# PCB_3U_VHDCI_Baseboard.net
KiCad netlist of a schematic drawn in Altium Designer
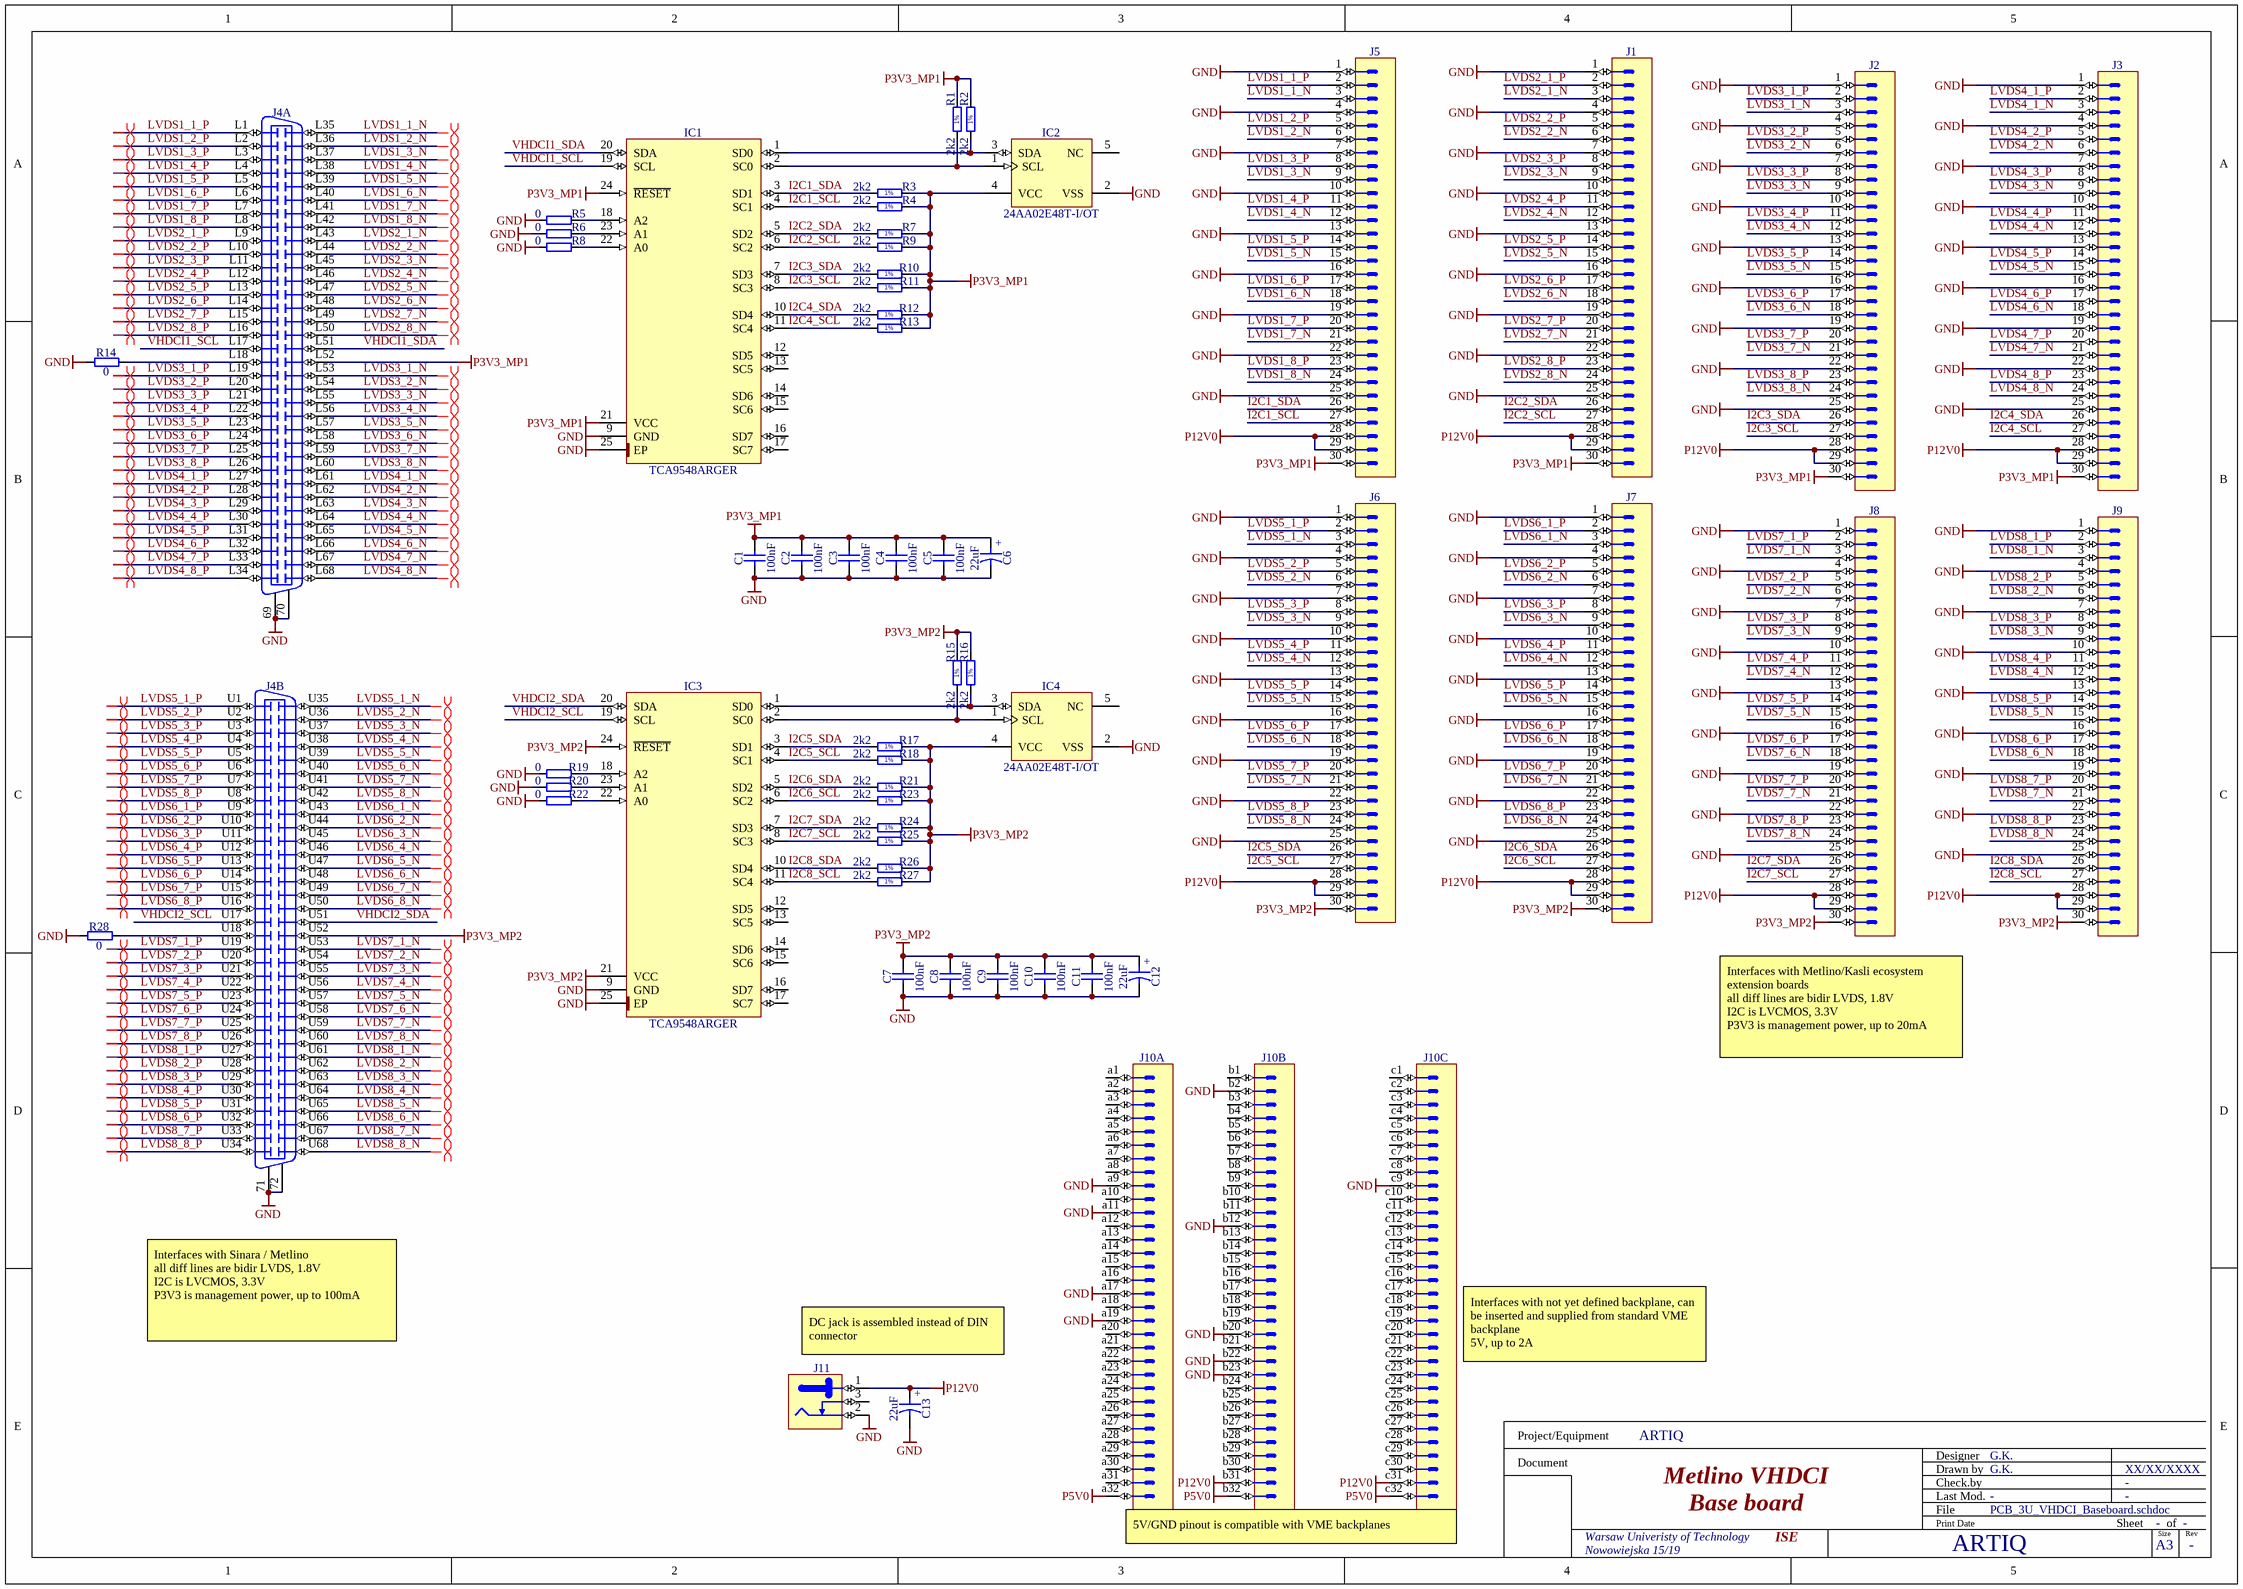
[diagram p0: PCB_3U_VHDCI_Baseboard.schdoc]

(export (version "E")
  (design (tool "Eeschema 10.0.6"))
  (components
    (comp (ref "C1")
      (value "100nF")
      (footprint "CAPC1005X55N")
      (description "Non-polarised capacitor")
      (fields
        (field (name "PART NUMBER") "CC0402_100NF_16V_10%_X5R")
        (field (name "VOLTAGE") "16V")
        (field (name "AUTHOR") "CERN DEM JLC")
      )
      (libsource (lib "Capacitors") (part "Capacitor - non polarized"))
    )
    (comp (ref "C2")
      (value "100nF")
      (footprint "CAPC1005X55N")
      (description "Non-polarised capacitor")
      (fields
        (field (name "PART NUMBER") "CC0402_100NF_16V_10%_X5R")
        (field (name "VOLTAGE") "16V")
        (field (name "AUTHOR") "CERN DEM JLC")
      )
      (libsource (lib "Capacitors") (part "Capacitor - non polarized"))
    )
    (comp (ref "C3")
      (value "100nF")
      (footprint "CAPC1005X55N")
      (description "Non-polarised capacitor")
      (fields
        (field (name "PART NUMBER") "CC0402_100NF_16V_10%_X5R")
        (field (name "VOLTAGE") "16V")
        (field (name "AUTHOR") "CERN DEM JLC")
      )
      (libsource (lib "Capacitors") (part "Capacitor - non polarized"))
    )
    (comp (ref "C4")
      (value "100nF")
      (footprint "CAPC1005X55N")
      (description "Non-polarised capacitor")
      (fields
        (field (name "PART NUMBER") "CC0402_100NF_16V_10%_X5R")
        (field (name "VOLTAGE") "16V")
        (field (name "AUTHOR") "CERN DEM JLC")
      )
      (libsource (lib "Capacitors") (part "Capacitor - non polarized"))
    )
    (comp (ref "C5")
      (value "100nF")
      (footprint "CAPC1005X55N")
      (description "Non-polarised capacitor")
      (fields
        (field (name "PART NUMBER") "CC0402_100NF_16V_10%_X5R")
        (field (name "VOLTAGE") "16V")
        (field (name "AUTHOR") "CERN DEM JLC")
      )
      (libsource (lib "Capacitors") (part "Capacitor - non polarized"))
    )
    (comp (ref "C6")
      (value "22uF")
      (footprint "CAPAE530X540N")
      (description "Polarised capacitor")
      (fields
        (field (name "PART NUMBER") "CAE530-540_22UF_16V_20%")
        (field (name "VOLTAGE") "16V")
        (field (name "AUTHOR") "CERN DEM JLC")
      )
      (libsource (lib "Capacitors") (part "Capacitor - polarized"))
    )
    (comp (ref "C7")
      (value "100nF")
      (footprint "CAPC1005X55N")
      (description "Non-polarised capacitor")
      (fields
        (field (name "PART NUMBER") "CC0402_100NF_16V_10%_X5R")
        (field (name "VOLTAGE") "16V")
        (field (name "AUTHOR") "CERN DEM JLC")
      )
      (libsource (lib "Capacitors") (part "Capacitor - non polarized"))
    )
    (comp (ref "C8")
      (value "100nF")
      (footprint "CAPC1005X55N")
      (description "Non-polarised capacitor")
      (fields
        (field (name "PART NUMBER") "CC0402_100NF_16V_10%_X5R")
        (field (name "VOLTAGE") "16V")
        (field (name "AUTHOR") "CERN DEM JLC")
      )
      (libsource (lib "Capacitors") (part "Capacitor - non polarized"))
    )
    (comp (ref "C9")
      (value "100nF")
      (footprint "CAPC1005X55N")
      (description "Non-polarised capacitor")
      (fields
        (field (name "PART NUMBER") "CC0402_100NF_16V_10%_X5R")
        (field (name "VOLTAGE") "16V")
        (field (name "AUTHOR") "CERN DEM JLC")
      )
      (libsource (lib "Capacitors") (part "Capacitor - non polarized"))
    )
    (comp (ref "C10")
      (value "100nF")
      (footprint "CAPC1005X55N")
      (description "Non-polarised capacitor")
      (fields
        (field (name "PART NUMBER") "CC0402_100NF_16V_10%_X5R")
        (field (name "VOLTAGE") "16V")
        (field (name "AUTHOR") "CERN DEM JLC")
      )
      (libsource (lib "Capacitors") (part "Capacitor - non polarized"))
    )
    (comp (ref "C11")
      (value "100nF")
      (footprint "CAPC1005X55N")
      (description "Non-polarised capacitor")
      (fields
        (field (name "PART NUMBER") "CC0402_100NF_16V_10%_X5R")
        (field (name "VOLTAGE") "16V")
        (field (name "AUTHOR") "CERN DEM JLC")
      )
      (libsource (lib "Capacitors") (part "Capacitor - non polarized"))
    )
    (comp (ref "C12")
      (value "22uF")
      (footprint "CAPAE530X540N")
      (description "Polarised capacitor")
      (fields
        (field (name "PART NUMBER") "CAE530-540_22UF_16V_20%")
        (field (name "VOLTAGE") "16V")
        (field (name "AUTHOR") "CERN DEM JLC")
      )
      (libsource (lib "Capacitors") (part "Capacitor - polarized"))
    )
    (comp (ref "C13")
      (value "22uF")
      (footprint "CAPAE530X540N")
      (description "Polarised capacitor")
      (fields
        (field (name "PART NUMBER") "CAE530-540_22UF_16V_20%")
        (field (name "VOLTAGE") "16V")
        (field (name "AUTHOR") "CERN DEM JLC")
      )
      (libsource (lib "Capacitors") (part "Capacitor - polarized"))
    )
    (comp (ref "IC1")
      (value "TCA9548ARGER")
      (footprint "QFN50P400X400X100-25N-S220")
      (description "Low Voltage 8-Channel I2C Switch With Reset")
      (fields (field (name "MANUFACTURER") "TEXAS INSTRUMENTS") (field (name "AUTHOR") "CERN DEM JLC"))
      (libsource (lib "ICs And Semiconductors") (part "TCA9548ARGER"))
    )
    (comp (ref "IC2")
      (value "24AA02E48T-I/OT")
      (footprint "SOT95P280X145-5N")
      (description "1.7V-5.5V, 2K I2C Serial EEPROM With EUI-48 Node Identity")
      (fields (field (name "MANUFACTURER") "MICROCHIP TECHNOLOGY") (field (name "AUTHOR") "CERN DEM MR"))
      (libsource (lib "ICs And Semiconductors") (part "24AA02E48T-I/OT"))
    )
    (comp (ref "IC3")
      (value "TCA9548ARGER")
      (footprint "QFN50P400X400X100-25N-S220")
      (description "Low Voltage 8-Channel I2C Switch With Reset")
      (fields (field (name "MANUFACTURER") "TEXAS INSTRUMENTS") (field (name "AUTHOR") "CERN DEM JLC"))
      (libsource (lib "ICs And Semiconductors") (part "TCA9548ARGER"))
    )
    (comp (ref "IC4")
      (value "24AA02E48T-I/OT")
      (footprint "SOT95P280X145-5N")
      (description "1.7V-5.5V, 2K I2C Serial EEPROM With EUI-48 Node Identity")
      (fields (field (name "MANUFACTURER") "MICROCHIP TECHNOLOGY") (field (name "AUTHOR") "CERN DEM MR"))
      (libsource (lib "ICs And Semiconductors") (part "24AA02E48T-I/OT"))
    )
    (comp (ref "J1")
      (value "~")
      (footprint "3M_N2530-6002RB")
      (description "Connector 30 Male")
      (fields
        (field (name "PART NUMBER") "3M_N2530-6002RB")
        (field (name "MANUFACTURER") "3M")
        (field (name "AUTHOR") "CERN DEM JLC")
      )
      (libsource (lib "Connectors") (part "Connector 30 Male"))
    )
    (comp (ref "J2")
      (value "~")
      (footprint "3M_N2530-6002RB")
      (description "Connector 30 Male")
      (fields
        (field (name "PART NUMBER") "3M_N2530-6002RB")
        (field (name "MANUFACTURER") "3M")
        (field (name "AUTHOR") "CERN DEM JLC")
      )
      (libsource (lib "Connectors") (part "Connector 30 Male"))
    )
    (comp (ref "J3")
      (value "~")
      (footprint "3M_N2530-6002RB")
      (description "Connector 30 Male")
      (fields
        (field (name "PART NUMBER") "3M_N2530-6002RB")
        (field (name "MANUFACTURER") "3M")
        (field (name "AUTHOR") "CERN DEM JLC")
      )
      (libsource (lib "Connectors") (part "Connector 30 Male"))
    )
    (comp (ref "J4")
      (value "VHDCI")
      (footprint "MOLEX_74337-0015")
      (description "Very High Density Cable Interconnect (VHDCI ) 2x68 Female")
      (fields
        (field (name "PART NUMBER") "MOLEX_74337-0015")
        (field (name "MANUFACTURER") "MOLEX")
        (field (name "AUTHOR") "CERN DEM JLC")
      )
      (libsource (lib "Connectors") (part "Connector VHDCI 2x68 Female"))
    )
    (comp (ref "J5")
      (value "~")
      (footprint "3M_N2530-6002RB")
      (description "Connector 30 Male")
      (fields
        (field (name "PART NUMBER") "3M_N2530-6002RB")
        (field (name "MANUFACTURER") "3M")
        (field (name "AUTHOR") "CERN DEM JLC")
      )
      (libsource (lib "Connectors") (part "Connector 30 Male"))
    )
    (comp (ref "J6")
      (value "~")
      (footprint "3M_N2530-6002RB")
      (description "Connector 30 Male")
      (fields
        (field (name "PART NUMBER") "3M_N2530-6002RB")
        (field (name "MANUFACTURER") "3M")
        (field (name "AUTHOR") "CERN DEM JLC")
      )
      (libsource (lib "Connectors") (part "Connector 30 Male"))
    )
    (comp (ref "J7")
      (value "~")
      (footprint "3M_N2530-6002RB")
      (description "Connector 30 Male")
      (fields
        (field (name "PART NUMBER") "3M_N2530-6002RB")
        (field (name "MANUFACTURER") "3M")
        (field (name "AUTHOR") "CERN DEM JLC")
      )
      (libsource (lib "Connectors") (part "Connector 30 Male"))
    )
    (comp (ref "J8")
      (value "~")
      (footprint "3M_N2530-6002RB")
      (description "Connector 30 Male")
      (fields
        (field (name "PART NUMBER") "3M_N2530-6002RB")
        (field (name "MANUFACTURER") "3M")
        (field (name "AUTHOR") "CERN DEM JLC")
      )
      (libsource (lib "Connectors") (part "Connector 30 Male"))
    )
    (comp (ref "J9")
      (value "~")
      (footprint "3M_N2530-6002RB")
      (description "Connector 30 Male")
      (fields
        (field (name "PART NUMBER") "3M_N2530-6002RB")
        (field (name "MANUFACTURER") "3M")
        (field (name "AUTHOR") "CERN DEM JLC")
      )
      (libsource (lib "Connectors") (part "Connector 30 Male"))
    )
    (comp (ref "J10")
      (value "DIN 41612 Type C")
      (footprint "HARTING_09 03 196 2921")
      (description "Connector 96abc male (3x32)")
      (fields
        (field (name "PART NUMBER") "HARTING_09 03 196 2921")
        (field (name "MANUFACTURER") "HARTING")
        (field (name "AUTHOR") "CERN DEM JLC")
      )
      (libsource (lib "Connectors") (part "Connector 96abc male (3x32)"))
    )
    (comp (ref "J11")
      (value "Jack")
      (footprint "CUI_PJ-102BH")
      (description "2.5 mm Center Pin, 5A, 24V Right Angle, Through Hole, Tapered Pins, DC Power Jack Connector")
      (fields
        (field (name "PART NUMBER") "CUI_PJ-102BH")
        (field (name "MANUFACTURER") "CUI INC.")
        (field (name "AUTHOR") "CERN DEM JLC")
      )
      (libsource (lib "Connectors") (part "CUI_PJ-102BH"))
    )
    (comp (ref "R1")
      (value "2k2")
      (footprint "RESC1005X40N")
      (description "Resistor - 1%")
      (fields
        (field (name "PART NUMBER") "R0402_2K2_1%_0.0625W_100PPM")
        (field (name "POWER") "0.0625W")
        (field (name "AUTHOR") "CERN DEM JLC")
      )
      (libsource (lib "Resistors") (part "Resistor - 1%"))
    )
    (comp (ref "R2")
      (value "2k2")
      (footprint "RESC1005X40N")
      (description "Resistor - 1%")
      (fields
        (field (name "PART NUMBER") "R0402_2K2_1%_0.0625W_100PPM")
        (field (name "POWER") "0.0625W")
        (field (name "AUTHOR") "CERN DEM JLC")
      )
      (libsource (lib "Resistors") (part "Resistor - 1%"))
    )
    (comp (ref "R3")
      (value "2k2")
      (footprint "RESC1005X40N")
      (description "Resistor - 1%")
      (fields
        (field (name "PART NUMBER") "R0402_2K2_1%_0.0625W_100PPM")
        (field (name "POWER") "0.0625W")
        (field (name "AUTHOR") "CERN DEM JLC")
      )
      (libsource (lib "Resistors") (part "Resistor - 1%"))
    )
    (comp (ref "R4")
      (value "2k2")
      (footprint "RESC1005X40N")
      (description "Resistor - 1%")
      (fields
        (field (name "PART NUMBER") "R0402_2K2_1%_0.0625W_100PPM")
        (field (name "POWER") "0.0625W")
        (field (name "AUTHOR") "CERN DEM JLC")
      )
      (libsource (lib "Resistors") (part "Resistor - 1%"))
    )
    (comp (ref "R5")
      (value "0")
      (footprint "RESC1005X40N")
      (description "Resistor")
      (fields
        (field (name "PART NUMBER") "R0402_0R_JUMPER")
        (field (name "MANUFACTURER") "GENERIC")
        (field (name "AUTHOR") "CERN DEM JLC")
      )
      (libsource (lib "Resistors") (part "Resistor"))
    )
    (comp (ref "R6")
      (value "0")
      (footprint "RESC1005X40N")
      (description "Resistor")
      (fields
        (field (name "PART NUMBER") "R0402_0R_JUMPER")
        (field (name "MANUFACTURER") "GENERIC")
        (field (name "AUTHOR") "CERN DEM JLC")
      )
      (libsource (lib "Resistors") (part "Resistor"))
    )
    (comp (ref "R7")
      (value "2k2")
      (footprint "RESC1005X40N")
      (description "Resistor - 1%")
      (fields
        (field (name "PART NUMBER") "R0402_2K2_1%_0.0625W_100PPM")
        (field (name "POWER") "0.0625W")
        (field (name "AUTHOR") "CERN DEM JLC")
      )
      (libsource (lib "Resistors") (part "Resistor - 1%"))
    )
    (comp (ref "R8")
      (value "0")
      (footprint "RESC1005X40N")
      (description "Resistor")
      (fields
        (field (name "PART NUMBER") "R0402_0R_JUMPER")
        (field (name "MANUFACTURER") "GENERIC")
        (field (name "AUTHOR") "CERN DEM JLC")
      )
      (libsource (lib "Resistors") (part "Resistor"))
    )
    (comp (ref "R9")
      (value "2k2")
      (footprint "RESC1005X40N")
      (description "Resistor - 1%")
      (fields
        (field (name "PART NUMBER") "R0402_2K2_1%_0.0625W_100PPM")
        (field (name "POWER") "0.0625W")
        (field (name "AUTHOR") "CERN DEM JLC")
      )
      (libsource (lib "Resistors") (part "Resistor - 1%"))
    )
    (comp (ref "R10")
      (value "2k2")
      (footprint "RESC1005X40N")
      (description "Resistor - 1%")
      (fields
        (field (name "PART NUMBER") "R0402_2K2_1%_0.0625W_100PPM")
        (field (name "POWER") "0.0625W")
        (field (name "AUTHOR") "CERN DEM JLC")
      )
      (libsource (lib "Resistors") (part "Resistor - 1%"))
    )
    (comp (ref "R11")
      (value "2k2")
      (footprint "RESC1005X40N")
      (description "Resistor - 1%")
      (fields
        (field (name "PART NUMBER") "R0402_2K2_1%_0.0625W_100PPM")
        (field (name "POWER") "0.0625W")
        (field (name "AUTHOR") "CERN DEM JLC")
      )
      (libsource (lib "Resistors") (part "Resistor - 1%"))
    )
    (comp (ref "R12")
      (value "2k2")
      (footprint "RESC1005X40N")
      (description "Resistor - 1%")
      (fields
        (field (name "PART NUMBER") "R0402_2K2_1%_0.0625W_100PPM")
        (field (name "POWER") "0.0625W")
        (field (name "AUTHOR") "CERN DEM JLC")
      )
      (libsource (lib "Resistors") (part "Resistor - 1%"))
    )
    (comp (ref "R13")
      (value "2k2")
      (footprint "RESC1005X40N")
      (description "Resistor - 1%")
      (fields
        (field (name "PART NUMBER") "R0402_2K2_1%_0.0625W_100PPM")
        (field (name "POWER") "0.0625W")
        (field (name "AUTHOR") "CERN DEM JLC")
      )
      (libsource (lib "Resistors") (part "Resistor - 1%"))
    )
    (comp (ref "R14")
      (value "0")
      (footprint "RESC1005X40N")
      (description "Resistor")
      (fields
        (field (name "PART NUMBER") "R0402_0R_JUMPER")
        (field (name "MANUFACTURER") "GENERIC")
        (field (name "AUTHOR") "CERN DEM JLC")
      )
      (libsource (lib "Resistors") (part "Resistor"))
    )
    (comp (ref "R15")
      (value "2k2")
      (footprint "RESC1005X40N")
      (description "Resistor - 1%")
      (fields
        (field (name "PART NUMBER") "R0402_2K2_1%_0.0625W_100PPM")
        (field (name "POWER") "0.0625W")
        (field (name "AUTHOR") "CERN DEM JLC")
      )
      (libsource (lib "Resistors") (part "Resistor - 1%"))
    )
    (comp (ref "R16")
      (value "2k2")
      (footprint "RESC1005X40N")
      (description "Resistor - 1%")
      (fields
        (field (name "PART NUMBER") "R0402_2K2_1%_0.0625W_100PPM")
        (field (name "POWER") "0.0625W")
        (field (name "AUTHOR") "CERN DEM JLC")
      )
      (libsource (lib "Resistors") (part "Resistor - 1%"))
    )
    (comp (ref "R17")
      (value "2k2")
      (footprint "RESC1005X40N")
      (description "Resistor - 1%")
      (fields
        (field (name "PART NUMBER") "R0402_2K2_1%_0.0625W_100PPM")
        (field (name "POWER") "0.0625W")
        (field (name "AUTHOR") "CERN DEM JLC")
      )
      (libsource (lib "Resistors") (part "Resistor - 1%"))
    )
    (comp (ref "R18")
      (value "2k2")
      (footprint "RESC1005X40N")
      (description "Resistor - 1%")
      (fields
        (field (name "PART NUMBER") "R0402_2K2_1%_0.0625W_100PPM")
        (field (name "POWER") "0.0625W")
        (field (name "AUTHOR") "CERN DEM JLC")
      )
      (libsource (lib "Resistors") (part "Resistor - 1%"))
    )
    (comp (ref "R19")
      (value "0")
      (footprint "RESC1005X40N")
      (description "Resistor")
      (fields
        (field (name "PART NUMBER") "R0402_0R_JUMPER")
        (field (name "MANUFACTURER") "GENERIC")
        (field (name "AUTHOR") "CERN DEM JLC")
      )
      (libsource (lib "Resistors") (part "Resistor"))
    )
    (comp (ref "R20")
      (value "0")
      (footprint "RESC1005X40N")
      (description "Resistor")
      (fields
        (field (name "PART NUMBER") "R0402_0R_JUMPER")
        (field (name "MANUFACTURER") "GENERIC")
        (field (name "AUTHOR") "CERN DEM JLC")
      )
      (libsource (lib "Resistors") (part "Resistor"))
    )
    (comp (ref "R21")
      (value "2k2")
      (footprint "RESC1005X40N")
      (description "Resistor - 1%")
      (fields
        (field (name "PART NUMBER") "R0402_2K2_1%_0.0625W_100PPM")
        (field (name "POWER") "0.0625W")
        (field (name "AUTHOR") "CERN DEM JLC")
      )
      (libsource (lib "Resistors") (part "Resistor - 1%"))
    )
    (comp (ref "R22")
      (value "0")
      (footprint "RESC1005X40N")
      (description "Resistor")
      (fields
        (field (name "PART NUMBER") "R0402_0R_JUMPER")
        (field (name "MANUFACTURER") "GENERIC")
        (field (name "AUTHOR") "CERN DEM JLC")
      )
      (libsource (lib "Resistors") (part "Resistor"))
    )
    (comp (ref "R23")
      (value "2k2")
      (footprint "RESC1005X40N")
      (description "Resistor - 1%")
      (fields
        (field (name "PART NUMBER") "R0402_2K2_1%_0.0625W_100PPM")
        (field (name "POWER") "0.0625W")
        (field (name "AUTHOR") "CERN DEM JLC")
      )
      (libsource (lib "Resistors") (part "Resistor - 1%"))
    )
    (comp (ref "R24")
      (value "2k2")
      (footprint "RESC1005X40N")
      (description "Resistor - 1%")
      (fields
        (field (name "PART NUMBER") "R0402_2K2_1%_0.0625W_100PPM")
        (field (name "POWER") "0.0625W")
        (field (name "AUTHOR") "CERN DEM JLC")
      )
      (libsource (lib "Resistors") (part "Resistor - 1%"))
    )
    (comp (ref "R25")
      (value "2k2")
      (footprint "RESC1005X40N")
      (description "Resistor - 1%")
      (fields
        (field (name "PART NUMBER") "R0402_2K2_1%_0.0625W_100PPM")
        (field (name "POWER") "0.0625W")
        (field (name "AUTHOR") "CERN DEM JLC")
      )
      (libsource (lib "Resistors") (part "Resistor - 1%"))
    )
    (comp (ref "R26")
      (value "2k2")
      (footprint "RESC1005X40N")
      (description "Resistor - 1%")
      (fields
        (field (name "PART NUMBER") "R0402_2K2_1%_0.0625W_100PPM")
        (field (name "POWER") "0.0625W")
        (field (name "AUTHOR") "CERN DEM JLC")
      )
      (libsource (lib "Resistors") (part "Resistor - 1%"))
    )
    (comp (ref "R27")
      (value "2k2")
      (footprint "RESC1005X40N")
      (description "Resistor - 1%")
      (fields
        (field (name "PART NUMBER") "R0402_2K2_1%_0.0625W_100PPM")
        (field (name "POWER") "0.0625W")
        (field (name "AUTHOR") "CERN DEM JLC")
      )
      (libsource (lib "Resistors") (part "Resistor - 1%"))
    )
    (comp (ref "R28")
      (value "0")
      (footprint "RESC1005X40N")
      (description "Resistor")
      (fields
        (field (name "PART NUMBER") "R0402_0R_JUMPER")
        (field (name "MANUFACTURER") "GENERIC")
        (field (name "AUTHOR") "CERN DEM JLC")
      )
      (libsource (lib "Resistors") (part "Resistor"))
    )
  )
  (nets
    (net (code "1") (name "/I2C1_SCL") (class "Default")
      (node (ref "IC1") (pin "4") (pinfunction "SC1_4") (pintype "bidirectional"))
      (node (ref "J5") (pin "27") (pinfunction "27_27") (pintype "bidirectional"))
      (node (ref "R4") (pin "1") (pinfunction "1_1") (pintype "passive"))
    )
    (net (code "2") (name "/I2C1_SDA") (class "Default")
      (node (ref "IC1") (pin "3") (pinfunction "SD1_3") (pintype "bidirectional"))
      (node (ref "J5") (pin "26") (pinfunction "26_26") (pintype "bidirectional"))
      (node (ref "R3") (pin "1") (pinfunction "1_1") (pintype "passive"))
    )
    (net (code "3") (name "/I2C2_SCL") (class "Default")
      (node (ref "IC1") (pin "6") (pinfunction "SC2_6") (pintype "bidirectional"))
      (node (ref "J1") (pin "27") (pinfunction "27_27") (pintype "bidirectional"))
      (node (ref "R9") (pin "1") (pinfunction "1_1") (pintype "passive"))
    )
    (net (code "4") (name "/I2C2_SDA") (class "Default")
      (node (ref "IC1") (pin "5") (pinfunction "SD2_5") (pintype "bidirectional"))
      (node (ref "J1") (pin "26") (pinfunction "26_26") (pintype "bidirectional"))
      (node (ref "R7") (pin "1") (pinfunction "1_1") (pintype "passive"))
    )
    (net (code "5") (name "/I2C3_SCL") (class "Default")
      (node (ref "IC1") (pin "8") (pinfunction "SC3_8") (pintype "bidirectional"))
      (node (ref "J2") (pin "27") (pinfunction "27_27") (pintype "bidirectional"))
      (node (ref "R11") (pin "1") (pinfunction "1_1") (pintype "passive"))
    )
    (net (code "6") (name "/I2C3_SDA") (class "Default")
      (node (ref "IC1") (pin "7") (pinfunction "SD3_7") (pintype "bidirectional"))
      (node (ref "J2") (pin "26") (pinfunction "26_26") (pintype "bidirectional"))
      (node (ref "R10") (pin "1") (pinfunction "1_1") (pintype "passive"))
    )
    (net (code "7") (name "/I2C4_SCL") (class "Default")
      (node (ref "IC1") (pin "11") (pinfunction "SC4_11") (pintype "bidirectional"))
      (node (ref "J3") (pin "27") (pinfunction "27_27") (pintype "bidirectional"))
      (node (ref "R13") (pin "1") (pinfunction "1_1") (pintype "passive"))
    )
    (net (code "8") (name "/I2C4_SDA") (class "Default")
      (node (ref "IC1") (pin "10") (pinfunction "SD4_10") (pintype "bidirectional"))
      (node (ref "J3") (pin "26") (pinfunction "26_26") (pintype "bidirectional"))
      (node (ref "R12") (pin "1") (pinfunction "1_1") (pintype "passive"))
    )
    (net (code "9") (name "/I2C5_SCL") (class "Default")
      (node (ref "IC3") (pin "4") (pinfunction "SC1_4") (pintype "bidirectional"))
      (node (ref "J6") (pin "27") (pinfunction "27_27") (pintype "bidirectional"))
      (node (ref "R18") (pin "1") (pinfunction "1_1") (pintype "passive"))
    )
    (net (code "10") (name "/I2C5_SDA") (class "Default")
      (node (ref "IC3") (pin "3") (pinfunction "SD1_3") (pintype "bidirectional"))
      (node (ref "J6") (pin "26") (pinfunction "26_26") (pintype "bidirectional"))
      (node (ref "R17") (pin "1") (pinfunction "1_1") (pintype "passive"))
    )
    (net (code "11") (name "/I2C6_SCL") (class "Default")
      (node (ref "IC3") (pin "6") (pinfunction "SC2_6") (pintype "bidirectional"))
      (node (ref "J7") (pin "27") (pinfunction "27_27") (pintype "bidirectional"))
      (node (ref "R23") (pin "1") (pinfunction "1_1") (pintype "passive"))
    )
    (net (code "12") (name "/I2C6_SDA") (class "Default")
      (node (ref "IC3") (pin "5") (pinfunction "SD2_5") (pintype "bidirectional"))
      (node (ref "J7") (pin "26") (pinfunction "26_26") (pintype "bidirectional"))
      (node (ref "R21") (pin "1") (pinfunction "1_1") (pintype "passive"))
    )
    (net (code "13") (name "/I2C7_SCL") (class "Default")
      (node (ref "IC3") (pin "8") (pinfunction "SC3_8") (pintype "bidirectional"))
      (node (ref "J8") (pin "27") (pinfunction "27_27") (pintype "bidirectional"))
      (node (ref "R25") (pin "1") (pinfunction "1_1") (pintype "passive"))
    )
    (net (code "14") (name "/I2C7_SDA") (class "Default")
      (node (ref "IC3") (pin "7") (pinfunction "SD3_7") (pintype "bidirectional"))
      (node (ref "J8") (pin "26") (pinfunction "26_26") (pintype "bidirectional"))
      (node (ref "R24") (pin "1") (pinfunction "1_1") (pintype "passive"))
    )
    (net (code "15") (name "/I2C8_SCL") (class "Default")
      (node (ref "IC3") (pin "11") (pinfunction "SC4_11") (pintype "bidirectional"))
      (node (ref "J9") (pin "27") (pinfunction "27_27") (pintype "bidirectional"))
      (node (ref "R27") (pin "1") (pinfunction "1_1") (pintype "passive"))
    )
    (net (code "16") (name "/I2C8_SDA") (class "Default")
      (node (ref "IC3") (pin "10") (pinfunction "SD4_10") (pintype "bidirectional"))
      (node (ref "J9") (pin "26") (pinfunction "26_26") (pintype "bidirectional"))
      (node (ref "R26") (pin "1") (pinfunction "1_1") (pintype "passive"))
    )
    (net (code "17") (name "/LVDS1_1_N") (class "Default")
      (node (ref "J4") (pin "L35") (pinfunction "35_L35") (pintype "bidirectional"))
      (node (ref "J5") (pin "3") (pinfunction "3_3") (pintype "bidirectional"))
    )
    (net (code "18") (name "/LVDS1_1_P") (class "Default")
      (node (ref "J4") (pin "L1") (pinfunction "1_L1") (pintype "bidirectional"))
      (node (ref "J5") (pin "2") (pinfunction "2_2") (pintype "bidirectional"))
    )
    (net (code "19") (name "/LVDS1_2_N") (class "Default")
      (node (ref "J4") (pin "L36") (pinfunction "36_L36") (pintype "bidirectional"))
      (node (ref "J5") (pin "6") (pinfunction "6_6") (pintype "bidirectional"))
    )
    (net (code "20") (name "/LVDS1_2_P") (class "Default")
      (node (ref "J4") (pin "L2") (pinfunction "2_L2") (pintype "bidirectional"))
      (node (ref "J5") (pin "5") (pinfunction "5_5") (pintype "bidirectional"))
    )
    (net (code "21") (name "/LVDS1_3_N") (class "Default")
      (node (ref "J4") (pin "L37") (pinfunction "37_L37") (pintype "bidirectional"))
      (node (ref "J5") (pin "9") (pinfunction "9_9") (pintype "bidirectional"))
    )
    (net (code "22") (name "/LVDS1_3_P") (class "Default")
      (node (ref "J4") (pin "L3") (pinfunction "3_L3") (pintype "bidirectional"))
      (node (ref "J5") (pin "8") (pinfunction "8_8") (pintype "bidirectional"))
    )
    (net (code "23") (name "/LVDS1_4_N") (class "Default")
      (node (ref "J4") (pin "L38") (pinfunction "38_L38") (pintype "bidirectional"))
      (node (ref "J5") (pin "12") (pinfunction "12_12") (pintype "bidirectional"))
    )
    (net (code "24") (name "/LVDS1_4_P") (class "Default")
      (node (ref "J4") (pin "L4") (pinfunction "4_L4") (pintype "bidirectional"))
      (node (ref "J5") (pin "11") (pinfunction "11_11") (pintype "bidirectional"))
    )
    (net (code "25") (name "/LVDS1_5_N") (class "Default")
      (node (ref "J4") (pin "L39") (pinfunction "39_L39") (pintype "bidirectional"))
      (node (ref "J5") (pin "15") (pinfunction "15_15") (pintype "bidirectional"))
    )
    (net (code "26") (name "/LVDS1_5_P") (class "Default")
      (node (ref "J4") (pin "L5") (pinfunction "5_L5") (pintype "bidirectional"))
      (node (ref "J5") (pin "14") (pinfunction "14_14") (pintype "bidirectional"))
    )
    (net (code "27") (name "/LVDS1_6_N") (class "Default")
      (node (ref "J4") (pin "L40") (pinfunction "40_L40") (pintype "bidirectional"))
      (node (ref "J5") (pin "18") (pinfunction "18_18") (pintype "bidirectional"))
    )
    (net (code "28") (name "/LVDS1_6_P") (class "Default")
      (node (ref "J4") (pin "L6") (pinfunction "6_L6") (pintype "bidirectional"))
      (node (ref "J5") (pin "17") (pinfunction "17_17") (pintype "bidirectional"))
    )
    (net (code "29") (name "/LVDS1_7_N") (class "Default")
      (node (ref "J4") (pin "L41") (pinfunction "41_L41") (pintype "bidirectional"))
      (node (ref "J5") (pin "21") (pinfunction "21_21") (pintype "bidirectional"))
    )
    (net (code "30") (name "/LVDS1_7_P") (class "Default")
      (node (ref "J4") (pin "L7") (pinfunction "7_L7") (pintype "bidirectional"))
      (node (ref "J5") (pin "20") (pinfunction "20_20") (pintype "bidirectional"))
    )
    (net (code "31") (name "/LVDS1_8_N") (class "Default")
      (node (ref "J4") (pin "L42") (pinfunction "42_L42") (pintype "bidirectional"))
      (node (ref "J5") (pin "24") (pinfunction "24_24") (pintype "bidirectional"))
    )
    (net (code "32") (name "/LVDS1_8_P") (class "Default")
      (node (ref "J4") (pin "L8") (pinfunction "8_L8") (pintype "bidirectional"))
      (node (ref "J5") (pin "23") (pinfunction "23_23") (pintype "bidirectional"))
    )
    (net (code "33") (name "/LVDS2_1_N") (class "Default")
      (node (ref "J1") (pin "3") (pinfunction "3_3") (pintype "bidirectional"))
      (node (ref "J4") (pin "L43") (pinfunction "43_L43") (pintype "bidirectional"))
    )
    (net (code "34") (name "/LVDS2_1_P") (class "Default")
      (node (ref "J1") (pin "2") (pinfunction "2_2") (pintype "bidirectional"))
      (node (ref "J4") (pin "L9") (pinfunction "9_L9") (pintype "bidirectional"))
    )
    (net (code "35") (name "/LVDS2_2_N") (class "Default")
      (node (ref "J1") (pin "6") (pinfunction "6_6") (pintype "bidirectional"))
      (node (ref "J4") (pin "L44") (pinfunction "44_L44") (pintype "bidirectional"))
    )
    (net (code "36") (name "/LVDS2_2_P") (class "Default")
      (node (ref "J1") (pin "5") (pinfunction "5_5") (pintype "bidirectional"))
      (node (ref "J4") (pin "L10") (pinfunction "10_L10") (pintype "bidirectional"))
    )
    (net (code "37") (name "/LVDS2_3_N") (class "Default")
      (node (ref "J1") (pin "9") (pinfunction "9_9") (pintype "bidirectional"))
      (node (ref "J4") (pin "L45") (pinfunction "45_L45") (pintype "bidirectional"))
    )
    (net (code "38") (name "/LVDS2_3_P") (class "Default")
      (node (ref "J1") (pin "8") (pinfunction "8_8") (pintype "bidirectional"))
      (node (ref "J4") (pin "L11") (pinfunction "11_L11") (pintype "bidirectional"))
    )
    (net (code "39") (name "/LVDS2_4_N") (class "Default")
      (node (ref "J1") (pin "12") (pinfunction "12_12") (pintype "bidirectional"))
      (node (ref "J4") (pin "L46") (pinfunction "46_L46") (pintype "bidirectional"))
    )
    (net (code "40") (name "/LVDS2_4_P") (class "Default")
      (node (ref "J1") (pin "11") (pinfunction "11_11") (pintype "bidirectional"))
      (node (ref "J4") (pin "L12") (pinfunction "12_L12") (pintype "bidirectional"))
    )
    (net (code "41") (name "/LVDS2_5_N") (class "Default")
      (node (ref "J1") (pin "15") (pinfunction "15_15") (pintype "bidirectional"))
      (node (ref "J4") (pin "L47") (pinfunction "47_L47") (pintype "bidirectional"))
    )
    (net (code "42") (name "/LVDS2_5_P") (class "Default")
      (node (ref "J1") (pin "14") (pinfunction "14_14") (pintype "bidirectional"))
      (node (ref "J4") (pin "L13") (pinfunction "13_L13") (pintype "bidirectional"))
    )
    (net (code "43") (name "/LVDS2_6_N") (class "Default")
      (node (ref "J1") (pin "18") (pinfunction "18_18") (pintype "bidirectional"))
      (node (ref "J4") (pin "L48") (pinfunction "48_L48") (pintype "bidirectional"))
    )
    (net (code "44") (name "/LVDS2_6_P") (class "Default")
      (node (ref "J1") (pin "17") (pinfunction "17_17") (pintype "bidirectional"))
      (node (ref "J4") (pin "L14") (pinfunction "14_L14") (pintype "bidirectional"))
    )
    (net (code "45") (name "/LVDS2_7_N") (class "Default")
      (node (ref "J1") (pin "21") (pinfunction "21_21") (pintype "bidirectional"))
      (node (ref "J4") (pin "L49") (pinfunction "49_L49") (pintype "bidirectional"))
    )
    (net (code "46") (name "/LVDS2_7_P") (class "Default")
      (node (ref "J1") (pin "20") (pinfunction "20_20") (pintype "bidirectional"))
      (node (ref "J4") (pin "L15") (pinfunction "15_L15") (pintype "bidirectional"))
    )
    (net (code "47") (name "/LVDS2_8_N") (class "Default")
      (node (ref "J1") (pin "24") (pinfunction "24_24") (pintype "bidirectional"))
      (node (ref "J4") (pin "L50") (pinfunction "50_L50") (pintype "bidirectional"))
    )
    (net (code "48") (name "/LVDS2_8_P") (class "Default")
      (node (ref "J1") (pin "23") (pinfunction "23_23") (pintype "bidirectional"))
      (node (ref "J4") (pin "L16") (pinfunction "16_L16") (pintype "bidirectional"))
    )
    (net (code "49") (name "/LVDS3_1_N") (class "Default")
      (node (ref "J2") (pin "3") (pinfunction "3_3") (pintype "bidirectional"))
      (node (ref "J4") (pin "L53") (pinfunction "53_L53") (pintype "bidirectional"))
    )
    (net (code "50") (name "/LVDS3_1_P") (class "Default")
      (node (ref "J2") (pin "2") (pinfunction "2_2") (pintype "bidirectional"))
      (node (ref "J4") (pin "L19") (pinfunction "19_L19") (pintype "bidirectional"))
    )
    (net (code "51") (name "/LVDS3_2_N") (class "Default")
      (node (ref "J2") (pin "6") (pinfunction "6_6") (pintype "bidirectional"))
      (node (ref "J4") (pin "L54") (pinfunction "54_L54") (pintype "bidirectional"))
    )
    (net (code "52") (name "/LVDS3_2_P") (class "Default")
      (node (ref "J2") (pin "5") (pinfunction "5_5") (pintype "bidirectional"))
      (node (ref "J4") (pin "L20") (pinfunction "20_L20") (pintype "bidirectional"))
    )
    (net (code "53") (name "/LVDS3_3_N") (class "Default")
      (node (ref "J2") (pin "9") (pinfunction "9_9") (pintype "bidirectional"))
      (node (ref "J4") (pin "L55") (pinfunction "55_L55") (pintype "bidirectional"))
    )
    (net (code "54") (name "/LVDS3_3_P") (class "Default")
      (node (ref "J2") (pin "8") (pinfunction "8_8") (pintype "bidirectional"))
      (node (ref "J4") (pin "L21") (pinfunction "21_L21") (pintype "bidirectional"))
    )
    (net (code "55") (name "/LVDS3_4_N") (class "Default")
      (node (ref "J2") (pin "12") (pinfunction "12_12") (pintype "bidirectional"))
      (node (ref "J4") (pin "L56") (pinfunction "56_L56") (pintype "bidirectional"))
    )
    (net (code "56") (name "/LVDS3_4_P") (class "Default")
      (node (ref "J2") (pin "11") (pinfunction "11_11") (pintype "bidirectional"))
      (node (ref "J4") (pin "L22") (pinfunction "22_L22") (pintype "bidirectional"))
    )
    (net (code "57") (name "/LVDS3_5_N") (class "Default")
      (node (ref "J2") (pin "15") (pinfunction "15_15") (pintype "bidirectional"))
      (node (ref "J4") (pin "L57") (pinfunction "57_L57") (pintype "bidirectional"))
    )
    (net (code "58") (name "/LVDS3_5_P") (class "Default")
      (node (ref "J2") (pin "14") (pinfunction "14_14") (pintype "bidirectional"))
      (node (ref "J4") (pin "L23") (pinfunction "23_L23") (pintype "bidirectional"))
    )
    (net (code "59") (name "/LVDS3_6_N") (class "Default")
      (node (ref "J2") (pin "18") (pinfunction "18_18") (pintype "bidirectional"))
      (node (ref "J4") (pin "L58") (pinfunction "58_L58") (pintype "bidirectional"))
    )
    (net (code "60") (name "/LVDS3_6_P") (class "Default")
      (node (ref "J2") (pin "17") (pinfunction "17_17") (pintype "bidirectional"))
      (node (ref "J4") (pin "L24") (pinfunction "24_L24") (pintype "bidirectional"))
    )
    (net (code "61") (name "/LVDS3_7_N") (class "Default")
      (node (ref "J2") (pin "21") (pinfunction "21_21") (pintype "bidirectional"))
      (node (ref "J4") (pin "L59") (pinfunction "59_L59") (pintype "bidirectional"))
    )
    (net (code "62") (name "/LVDS3_7_P") (class "Default")
      (node (ref "J2") (pin "20") (pinfunction "20_20") (pintype "bidirectional"))
      (node (ref "J4") (pin "L25") (pinfunction "25_L25") (pintype "bidirectional"))
    )
    (net (code "63") (name "/LVDS3_8_N") (class "Default")
      (node (ref "J2") (pin "24") (pinfunction "24_24") (pintype "bidirectional"))
      (node (ref "J4") (pin "L60") (pinfunction "60_L60") (pintype "bidirectional"))
    )
    (net (code "64") (name "/LVDS3_8_P") (class "Default")
      (node (ref "J2") (pin "23") (pinfunction "23_23") (pintype "bidirectional"))
      (node (ref "J4") (pin "L26") (pinfunction "26_L26") (pintype "bidirectional"))
    )
    (net (code "65") (name "/LVDS4_1_N") (class "Default")
      (node (ref "J3") (pin "3") (pinfunction "3_3") (pintype "bidirectional"))
      (node (ref "J4") (pin "L61") (pinfunction "61_L61") (pintype "bidirectional"))
    )
    (net (code "66") (name "/LVDS4_1_P") (class "Default")
      (node (ref "J3") (pin "2") (pinfunction "2_2") (pintype "bidirectional"))
      (node (ref "J4") (pin "L27") (pinfunction "27_L27") (pintype "bidirectional"))
    )
    (net (code "67") (name "/LVDS4_2_N") (class "Default")
      (node (ref "J3") (pin "6") (pinfunction "6_6") (pintype "bidirectional"))
      (node (ref "J4") (pin "L62") (pinfunction "62_L62") (pintype "bidirectional"))
    )
    (net (code "68") (name "/LVDS4_2_P") (class "Default")
      (node (ref "J3") (pin "5") (pinfunction "5_5") (pintype "bidirectional"))
      (node (ref "J4") (pin "L28") (pinfunction "28_L28") (pintype "bidirectional"))
    )
    (net (code "69") (name "/LVDS4_3_N") (class "Default")
      (node (ref "J3") (pin "9") (pinfunction "9_9") (pintype "bidirectional"))
      (node (ref "J4") (pin "L63") (pinfunction "63_L63") (pintype "bidirectional"))
    )
    (net (code "70") (name "/LVDS4_3_P") (class "Default")
      (node (ref "J3") (pin "8") (pinfunction "8_8") (pintype "bidirectional"))
      (node (ref "J4") (pin "L29") (pinfunction "29_L29") (pintype "bidirectional"))
    )
    (net (code "71") (name "/LVDS4_4_N") (class "Default")
      (node (ref "J3") (pin "12") (pinfunction "12_12") (pintype "bidirectional"))
      (node (ref "J4") (pin "L64") (pinfunction "64_L64") (pintype "bidirectional"))
    )
    (net (code "72") (name "/LVDS4_4_P") (class "Default")
      (node (ref "J3") (pin "11") (pinfunction "11_11") (pintype "bidirectional"))
      (node (ref "J4") (pin "L30") (pinfunction "30_L30") (pintype "bidirectional"))
    )
    (net (code "73") (name "/LVDS4_5_N") (class "Default")
      (node (ref "J3") (pin "15") (pinfunction "15_15") (pintype "bidirectional"))
      (node (ref "J4") (pin "L65") (pinfunction "65_L65") (pintype "bidirectional"))
    )
    (net (code "74") (name "/LVDS4_5_P") (class "Default")
      (node (ref "J3") (pin "14") (pinfunction "14_14") (pintype "bidirectional"))
      (node (ref "J4") (pin "L31") (pinfunction "31_L31") (pintype "bidirectional"))
    )
    (net (code "75") (name "/LVDS4_6_N") (class "Default")
      (node (ref "J3") (pin "18") (pinfunction "18_18") (pintype "bidirectional"))
      (node (ref "J4") (pin "L66") (pinfunction "66_L66") (pintype "bidirectional"))
    )
    (net (code "76") (name "/LVDS4_6_P") (class "Default")
      (node (ref "J3") (pin "17") (pinfunction "17_17") (pintype "bidirectional"))
      (node (ref "J4") (pin "L32") (pinfunction "32_L32") (pintype "bidirectional"))
    )
    (net (code "77") (name "/LVDS4_7_N") (class "Default")
      (node (ref "J3") (pin "21") (pinfunction "21_21") (pintype "bidirectional"))
      (node (ref "J4") (pin "L67") (pinfunction "67_L67") (pintype "bidirectional"))
    )
    (net (code "78") (name "/LVDS4_7_P") (class "Default")
      (node (ref "J3") (pin "20") (pinfunction "20_20") (pintype "bidirectional"))
      (node (ref "J4") (pin "L33") (pinfunction "33_L33") (pintype "bidirectional"))
    )
    (net (code "79") (name "/LVDS4_8_N") (class "Default")
      (node (ref "J3") (pin "24") (pinfunction "24_24") (pintype "bidirectional"))
      (node (ref "J4") (pin "L68") (pinfunction "68_L68") (pintype "bidirectional"))
    )
    (net (code "80") (name "/LVDS4_8_P") (class "Default")
      (node (ref "J3") (pin "23") (pinfunction "23_23") (pintype "bidirectional"))
      (node (ref "J4") (pin "L34") (pinfunction "34_L34") (pintype "bidirectional"))
    )
    (net (code "81") (name "/LVDS5_1_N") (class "Default")
      (node (ref "J4") (pin "U35") (pinfunction "35_U35") (pintype "bidirectional"))
      (node (ref "J6") (pin "3") (pinfunction "3_3") (pintype "bidirectional"))
    )
    (net (code "82") (name "/LVDS5_1_P") (class "Default")
      (node (ref "J4") (pin "U1") (pinfunction "1_U1") (pintype "bidirectional"))
      (node (ref "J6") (pin "2") (pinfunction "2_2") (pintype "bidirectional"))
    )
    (net (code "83") (name "/LVDS5_2_N") (class "Default")
      (node (ref "J4") (pin "U36") (pinfunction "36_U36") (pintype "bidirectional"))
      (node (ref "J6") (pin "6") (pinfunction "6_6") (pintype "bidirectional"))
    )
    (net (code "84") (name "/LVDS5_2_P") (class "Default")
      (node (ref "J4") (pin "U2") (pinfunction "2_U2") (pintype "bidirectional"))
      (node (ref "J6") (pin "5") (pinfunction "5_5") (pintype "bidirectional"))
    )
    (net (code "85") (name "/LVDS5_3_N") (class "Default")
      (node (ref "J4") (pin "U37") (pinfunction "37_U37") (pintype "bidirectional"))
      (node (ref "J6") (pin "9") (pinfunction "9_9") (pintype "bidirectional"))
    )
    (net (code "86") (name "/LVDS5_3_P") (class "Default")
      (node (ref "J4") (pin "U3") (pinfunction "3_U3") (pintype "bidirectional"))
      (node (ref "J6") (pin "8") (pinfunction "8_8") (pintype "bidirectional"))
    )
    (net (code "87") (name "/LVDS5_4_N") (class "Default")
      (node (ref "J4") (pin "U38") (pinfunction "38_U38") (pintype "bidirectional"))
      (node (ref "J6") (pin "12") (pinfunction "12_12") (pintype "bidirectional"))
    )
    (net (code "88") (name "/LVDS5_4_P") (class "Default")
      (node (ref "J4") (pin "U4") (pinfunction "4_U4") (pintype "bidirectional"))
      (node (ref "J6") (pin "11") (pinfunction "11_11") (pintype "bidirectional"))
    )
    (net (code "89") (name "/LVDS5_5_N") (class "Default")
      (node (ref "J4") (pin "U39") (pinfunction "39_U39") (pintype "bidirectional"))
      (node (ref "J6") (pin "15") (pinfunction "15_15") (pintype "bidirectional"))
    )
    (net (code "90") (name "/LVDS5_5_P") (class "Default")
      (node (ref "J4") (pin "U5") (pinfunction "5_U5") (pintype "bidirectional"))
      (node (ref "J6") (pin "14") (pinfunction "14_14") (pintype "bidirectional"))
    )
    (net (code "91") (name "/LVDS5_6_N") (class "Default")
      (node (ref "J4") (pin "U40") (pinfunction "40_U40") (pintype "bidirectional"))
      (node (ref "J6") (pin "18") (pinfunction "18_18") (pintype "bidirectional"))
    )
    (net (code "92") (name "/LVDS5_6_P") (class "Default")
      (node (ref "J4") (pin "U6") (pinfunction "6_U6") (pintype "bidirectional"))
      (node (ref "J6") (pin "17") (pinfunction "17_17") (pintype "bidirectional"))
    )
    (net (code "93") (name "/LVDS5_7_N") (class "Default")
      (node (ref "J4") (pin "U41") (pinfunction "41_U41") (pintype "bidirectional"))
      (node (ref "J6") (pin "21") (pinfunction "21_21") (pintype "bidirectional"))
    )
    (net (code "94") (name "/LVDS5_7_P") (class "Default")
      (node (ref "J4") (pin "U7") (pinfunction "7_U7") (pintype "bidirectional"))
      (node (ref "J6") (pin "20") (pinfunction "20_20") (pintype "bidirectional"))
    )
    (net (code "95") (name "/LVDS5_8_N") (class "Default")
      (node (ref "J4") (pin "U42") (pinfunction "42_U42") (pintype "bidirectional"))
      (node (ref "J6") (pin "24") (pinfunction "24_24") (pintype "bidirectional"))
    )
    (net (code "96") (name "/LVDS5_8_P") (class "Default")
      (node (ref "J4") (pin "U8") (pinfunction "8_U8") (pintype "bidirectional"))
      (node (ref "J6") (pin "23") (pinfunction "23_23") (pintype "bidirectional"))
    )
    (net (code "97") (name "/LVDS6_1_N") (class "Default")
      (node (ref "J4") (pin "U43") (pinfunction "43_U43") (pintype "bidirectional"))
      (node (ref "J7") (pin "3") (pinfunction "3_3") (pintype "bidirectional"))
    )
    (net (code "98") (name "/LVDS6_1_P") (class "Default")
      (node (ref "J4") (pin "U9") (pinfunction "9_U9") (pintype "bidirectional"))
      (node (ref "J7") (pin "2") (pinfunction "2_2") (pintype "bidirectional"))
    )
    (net (code "99") (name "/LVDS6_2_N") (class "Default")
      (node (ref "J4") (pin "U44") (pinfunction "44_U44") (pintype "bidirectional"))
      (node (ref "J7") (pin "6") (pinfunction "6_6") (pintype "bidirectional"))
    )
    (net (code "100") (name "/LVDS6_2_P") (class "Default")
      (node (ref "J4") (pin "U10") (pinfunction "10_U10") (pintype "bidirectional"))
      (node (ref "J7") (pin "5") (pinfunction "5_5") (pintype "bidirectional"))
    )
    (net (code "101") (name "/LVDS6_3_N") (class "Default")
      (node (ref "J4") (pin "U45") (pinfunction "45_U45") (pintype "bidirectional"))
      (node (ref "J7") (pin "9") (pinfunction "9_9") (pintype "bidirectional"))
    )
    (net (code "102") (name "/LVDS6_3_P") (class "Default")
      (node (ref "J4") (pin "U11") (pinfunction "11_U11") (pintype "bidirectional"))
      (node (ref "J7") (pin "8") (pinfunction "8_8") (pintype "bidirectional"))
    )
    (net (code "103") (name "/LVDS6_4_N") (class "Default")
      (node (ref "J4") (pin "U46") (pinfunction "46_U46") (pintype "bidirectional"))
      (node (ref "J7") (pin "12") (pinfunction "12_12") (pintype "bidirectional"))
    )
    (net (code "104") (name "/LVDS6_4_P") (class "Default")
      (node (ref "J4") (pin "U12") (pinfunction "12_U12") (pintype "bidirectional"))
      (node (ref "J7") (pin "11") (pinfunction "11_11") (pintype "bidirectional"))
    )
    (net (code "105") (name "/LVDS6_5_N") (class "Default")
      (node (ref "J4") (pin "U47") (pinfunction "47_U47") (pintype "bidirectional"))
      (node (ref "J7") (pin "15") (pinfunction "15_15") (pintype "bidirectional"))
    )
    (net (code "106") (name "/LVDS6_5_P") (class "Default")
      (node (ref "J4") (pin "U13") (pinfunction "13_U13") (pintype "bidirectional"))
      (node (ref "J7") (pin "14") (pinfunction "14_14") (pintype "bidirectional"))
    )
    (net (code "107") (name "/LVDS6_6_N") (class "Default")
      (node (ref "J4") (pin "U48") (pinfunction "48_U48") (pintype "bidirectional"))
      (node (ref "J7") (pin "18") (pinfunction "18_18") (pintype "bidirectional"))
    )
    (net (code "108") (name "/LVDS6_6_P") (class "Default")
      (node (ref "J4") (pin "U14") (pinfunction "14_U14") (pintype "bidirectional"))
      (node (ref "J7") (pin "17") (pinfunction "17_17") (pintype "bidirectional"))
    )
    (net (code "109") (name "/LVDS6_7_N") (class "Default")
      (node (ref "J4") (pin "U49") (pinfunction "49_U49") (pintype "bidirectional"))
      (node (ref "J7") (pin "21") (pinfunction "21_21") (pintype "bidirectional"))
    )
    (net (code "110") (name "/LVDS6_7_P") (class "Default")
      (node (ref "J4") (pin "U15") (pinfunction "15_U15") (pintype "bidirectional"))
      (node (ref "J7") (pin "20") (pinfunction "20_20") (pintype "bidirectional"))
    )
    (net (code "111") (name "/LVDS6_8_N") (class "Default")
      (node (ref "J4") (pin "U50") (pinfunction "50_U50") (pintype "bidirectional"))
      (node (ref "J7") (pin "24") (pinfunction "24_24") (pintype "bidirectional"))
    )
    (net (code "112") (name "/LVDS6_8_P") (class "Default")
      (node (ref "J4") (pin "U16") (pinfunction "16_U16") (pintype "bidirectional"))
      (node (ref "J7") (pin "23") (pinfunction "23_23") (pintype "bidirectional"))
    )
    (net (code "113") (name "/LVDS7_1_N") (class "Default")
      (node (ref "J4") (pin "U53") (pinfunction "53_U53") (pintype "bidirectional"))
      (node (ref "J8") (pin "3") (pinfunction "3_3") (pintype "bidirectional"))
    )
    (net (code "114") (name "/LVDS7_1_P") (class "Default")
      (node (ref "J4") (pin "U19") (pinfunction "19_U19") (pintype "bidirectional"))
      (node (ref "J8") (pin "2") (pinfunction "2_2") (pintype "bidirectional"))
    )
    (net (code "115") (name "/LVDS7_2_N") (class "Default")
      (node (ref "J4") (pin "U54") (pinfunction "54_U54") (pintype "bidirectional"))
      (node (ref "J8") (pin "6") (pinfunction "6_6") (pintype "bidirectional"))
    )
    (net (code "116") (name "/LVDS7_2_P") (class "Default")
      (node (ref "J4") (pin "U20") (pinfunction "20_U20") (pintype "bidirectional"))
      (node (ref "J8") (pin "5") (pinfunction "5_5") (pintype "bidirectional"))
    )
    (net (code "117") (name "/LVDS7_3_N") (class "Default")
      (node (ref "J4") (pin "U55") (pinfunction "55_U55") (pintype "bidirectional"))
      (node (ref "J8") (pin "9") (pinfunction "9_9") (pintype "bidirectional"))
    )
    (net (code "118") (name "/LVDS7_3_P") (class "Default")
      (node (ref "J4") (pin "U21") (pinfunction "21_U21") (pintype "bidirectional"))
      (node (ref "J8") (pin "8") (pinfunction "8_8") (pintype "bidirectional"))
    )
    (net (code "119") (name "/LVDS7_4_N") (class "Default")
      (node (ref "J4") (pin "U56") (pinfunction "56_U56") (pintype "bidirectional"))
      (node (ref "J8") (pin "12") (pinfunction "12_12") (pintype "bidirectional"))
    )
    (net (code "120") (name "/LVDS7_4_P") (class "Default")
      (node (ref "J4") (pin "U22") (pinfunction "22_U22") (pintype "bidirectional"))
      (node (ref "J8") (pin "11") (pinfunction "11_11") (pintype "bidirectional"))
    )
    (net (code "121") (name "/LVDS7_5_N") (class "Default")
      (node (ref "J4") (pin "U57") (pinfunction "57_U57") (pintype "bidirectional"))
      (node (ref "J8") (pin "15") (pinfunction "15_15") (pintype "bidirectional"))
    )
    (net (code "122") (name "/LVDS7_5_P") (class "Default")
      (node (ref "J4") (pin "U23") (pinfunction "23_U23") (pintype "bidirectional"))
      (node (ref "J8") (pin "14") (pinfunction "14_14") (pintype "bidirectional"))
    )
    (net (code "123") (name "/LVDS7_6_N") (class "Default")
      (node (ref "J4") (pin "U58") (pinfunction "58_U58") (pintype "bidirectional"))
      (node (ref "J8") (pin "18") (pinfunction "18_18") (pintype "bidirectional"))
    )
    (net (code "124") (name "/LVDS7_6_P") (class "Default")
      (node (ref "J4") (pin "U24") (pinfunction "24_U24") (pintype "bidirectional"))
      (node (ref "J8") (pin "17") (pinfunction "17_17") (pintype "bidirectional"))
    )
    (net (code "125") (name "/LVDS7_7_N") (class "Default")
      (node (ref "J4") (pin "U59") (pinfunction "59_U59") (pintype "bidirectional"))
      (node (ref "J8") (pin "21") (pinfunction "21_21") (pintype "bidirectional"))
    )
    (net (code "126") (name "/LVDS7_7_P") (class "Default")
      (node (ref "J4") (pin "U25") (pinfunction "25_U25") (pintype "bidirectional"))
      (node (ref "J8") (pin "20") (pinfunction "20_20") (pintype "bidirectional"))
    )
    (net (code "127") (name "/LVDS7_8_N") (class "Default")
      (node (ref "J4") (pin "U60") (pinfunction "60_U60") (pintype "bidirectional"))
      (node (ref "J8") (pin "24") (pinfunction "24_24") (pintype "bidirectional"))
    )
    (net (code "128") (name "/LVDS7_8_P") (class "Default")
      (node (ref "J4") (pin "U26") (pinfunction "26_U26") (pintype "bidirectional"))
      (node (ref "J8") (pin "23") (pinfunction "23_23") (pintype "bidirectional"))
    )
    (net (code "129") (name "/LVDS8_1_N") (class "Default")
      (node (ref "J4") (pin "U61") (pinfunction "61_U61") (pintype "bidirectional"))
      (node (ref "J9") (pin "3") (pinfunction "3_3") (pintype "bidirectional"))
    )
    (net (code "130") (name "/LVDS8_1_P") (class "Default")
      (node (ref "J4") (pin "U27") (pinfunction "27_U27") (pintype "bidirectional"))
      (node (ref "J9") (pin "2") (pinfunction "2_2") (pintype "bidirectional"))
    )
    (net (code "131") (name "/LVDS8_2_N") (class "Default")
      (node (ref "J4") (pin "U62") (pinfunction "62_U62") (pintype "bidirectional"))
      (node (ref "J9") (pin "6") (pinfunction "6_6") (pintype "bidirectional"))
    )
    (net (code "132") (name "/LVDS8_2_P") (class "Default")
      (node (ref "J4") (pin "U28") (pinfunction "28_U28") (pintype "bidirectional"))
      (node (ref "J9") (pin "5") (pinfunction "5_5") (pintype "bidirectional"))
    )
    (net (code "133") (name "/LVDS8_3_N") (class "Default")
      (node (ref "J4") (pin "U63") (pinfunction "63_U63") (pintype "bidirectional"))
      (node (ref "J9") (pin "9") (pinfunction "9_9") (pintype "bidirectional"))
    )
    (net (code "134") (name "/LVDS8_3_P") (class "Default")
      (node (ref "J4") (pin "U29") (pinfunction "29_U29") (pintype "bidirectional"))
      (node (ref "J9") (pin "8") (pinfunction "8_8") (pintype "bidirectional"))
    )
    (net (code "135") (name "/LVDS8_4_N") (class "Default")
      (node (ref "J4") (pin "U64") (pinfunction "64_U64") (pintype "bidirectional"))
      (node (ref "J9") (pin "12") (pinfunction "12_12") (pintype "bidirectional"))
    )
    (net (code "136") (name "/LVDS8_4_P") (class "Default")
      (node (ref "J4") (pin "U30") (pinfunction "30_U30") (pintype "bidirectional"))
      (node (ref "J9") (pin "11") (pinfunction "11_11") (pintype "bidirectional"))
    )
    (net (code "137") (name "/LVDS8_5_N") (class "Default")
      (node (ref "J4") (pin "U65") (pinfunction "65_U65") (pintype "bidirectional"))
      (node (ref "J9") (pin "15") (pinfunction "15_15") (pintype "bidirectional"))
    )
    (net (code "138") (name "/LVDS8_5_P") (class "Default")
      (node (ref "J4") (pin "U31") (pinfunction "31_U31") (pintype "bidirectional"))
      (node (ref "J9") (pin "14") (pinfunction "14_14") (pintype "bidirectional"))
    )
    (net (code "139") (name "/LVDS8_6_N") (class "Default")
      (node (ref "J4") (pin "U66") (pinfunction "66_U66") (pintype "bidirectional"))
      (node (ref "J9") (pin "18") (pinfunction "18_18") (pintype "bidirectional"))
    )
    (net (code "140") (name "/LVDS8_6_P") (class "Default")
      (node (ref "J4") (pin "U32") (pinfunction "32_U32") (pintype "bidirectional"))
      (node (ref "J9") (pin "17") (pinfunction "17_17") (pintype "bidirectional"))
    )
    (net (code "141") (name "/LVDS8_7_N") (class "Default")
      (node (ref "J4") (pin "U67") (pinfunction "67_U67") (pintype "bidirectional"))
      (node (ref "J9") (pin "21") (pinfunction "21_21") (pintype "bidirectional"))
    )
    (net (code "142") (name "/LVDS8_7_P") (class "Default")
      (node (ref "J4") (pin "U33") (pinfunction "33_U33") (pintype "bidirectional"))
      (node (ref "J9") (pin "20") (pinfunction "20_20") (pintype "bidirectional"))
    )
    (net (code "143") (name "/LVDS8_8_N") (class "Default")
      (node (ref "J4") (pin "U68") (pinfunction "68_U68") (pintype "bidirectional"))
      (node (ref "J9") (pin "24") (pinfunction "24_24") (pintype "bidirectional"))
    )
    (net (code "144") (name "/LVDS8_8_P") (class "Default")
      (node (ref "J4") (pin "U34") (pinfunction "34_U34") (pintype "bidirectional"))
      (node (ref "J9") (pin "23") (pinfunction "23_23") (pintype "bidirectional"))
    )
    (net (code "145") (name "/VHDCI1_SCL") (class "Default")
      (node (ref "IC1") (pin "19") (pinfunction "SCL_19") (pintype "bidirectional"))
      (node (ref "J4") (pin "L17") (pinfunction "17_L17") (pintype "bidirectional"))
    )
    (net (code "146") (name "/VHDCI1_SDA") (class "Default")
      (node (ref "IC1") (pin "20") (pinfunction "SDA_20") (pintype "bidirectional"))
      (node (ref "J4") (pin "L51") (pinfunction "51_L51") (pintype "bidirectional"))
    )
    (net (code "147") (name "/VHDCI2_SCL") (class "Default")
      (node (ref "IC3") (pin "19") (pinfunction "SCL_19") (pintype "bidirectional"))
      (node (ref "J4") (pin "U17") (pinfunction "17_U17") (pintype "bidirectional"))
    )
    (net (code "148") (name "/VHDCI2_SDA") (class "Default")
      (node (ref "IC3") (pin "20") (pinfunction "SDA_20") (pintype "bidirectional"))
      (node (ref "J4") (pin "U51") (pinfunction "51_U51") (pintype "bidirectional"))
    )
    (net (code "149") (name "GND") (class "Default")
      (node (ref "C1") (pin "1") (pinfunction "1_1") (pintype "passive"))
      (node (ref "C10") (pin "1") (pinfunction "1_1") (pintype "passive"))
      (node (ref "C11") (pin "1") (pinfunction "1_1") (pintype "passive"))
      (node (ref "C12") (pin "2") (pinfunction "2_2") (pintype "passive"))
      (node (ref "C13") (pin "2") (pinfunction "2_2") (pintype "passive"))
      (node (ref "C2") (pin "1") (pinfunction "1_1") (pintype "passive"))
      (node (ref "C3") (pin "1") (pinfunction "1_1") (pintype "passive"))
      (node (ref "C4") (pin "1") (pinfunction "1_1") (pintype "passive"))
      (node (ref "C5") (pin "1") (pinfunction "1_1") (pintype "passive"))
      (node (ref "C6") (pin "2") (pinfunction "2_2") (pintype "passive"))
      (node (ref "C7") (pin "1") (pinfunction "1_1") (pintype "passive"))
      (node (ref "C8") (pin "1") (pinfunction "1_1") (pintype "passive"))
      (node (ref "C9") (pin "1") (pinfunction "1_1") (pintype "passive"))
      (node (ref "IC1") (pin "25") (pinfunction "EP_25") (pintype "power_in"))
      (node (ref "IC1") (pin "9") (pinfunction "GND_9") (pintype "power_in"))
      (node (ref "IC2") (pin "2") (pinfunction "VSS_2") (pintype "power_in"))
      (node (ref "IC3") (pin "25") (pinfunction "EP_25") (pintype "power_in"))
      (node (ref "IC3") (pin "9") (pinfunction "GND_9") (pintype "power_in"))
      (node (ref "IC4") (pin "2") (pinfunction "VSS_2") (pintype "power_in"))
      (node (ref "J1") (pin "1") (pinfunction "1_1") (pintype "bidirectional"))
      (node (ref "J1") (pin "10") (pinfunction "10_10") (pintype "bidirectional"))
      (node (ref "J1") (pin "13") (pinfunction "13_13") (pintype "bidirectional"))
      (node (ref "J1") (pin "16") (pinfunction "16_16") (pintype "bidirectional"))
      (node (ref "J1") (pin "19") (pinfunction "19_19") (pintype "bidirectional"))
      (node (ref "J1") (pin "22") (pinfunction "22_22") (pintype "bidirectional"))
      (node (ref "J1") (pin "25") (pinfunction "25_25") (pintype "bidirectional"))
      (node (ref "J1") (pin "4") (pinfunction "4_4") (pintype "bidirectional"))
      (node (ref "J1") (pin "7") (pinfunction "7_7") (pintype "bidirectional"))
      (node (ref "J10") (pin "a11") (pinfunction "a11_a11") (pintype "bidirectional"))
      (node (ref "J10") (pin "a17") (pinfunction "a17_a17") (pintype "bidirectional"))
      (node (ref "J10") (pin "a19") (pinfunction "a19_a19") (pintype "bidirectional"))
      (node (ref "J10") (pin "a9") (pinfunction "a9_a9") (pintype "bidirectional"))
      (node (ref "J10") (pin "b12") (pinfunction "b12_b12") (pintype "bidirectional"))
      (node (ref "J10") (pin "b2") (pinfunction "b2_b2") (pintype "bidirectional"))
      (node (ref "J10") (pin "b20") (pinfunction "b20_b20") (pintype "bidirectional"))
      (node (ref "J10") (pin "b22") (pinfunction "b22_b22") (pintype "bidirectional"))
      (node (ref "J10") (pin "b23") (pinfunction "b23_b23") (pintype "bidirectional"))
      (node (ref "J10") (pin "c9") (pinfunction "c9_c9") (pintype "bidirectional"))
      (node (ref "J11") (pin "2") (pinfunction "2_2") (pintype "bidirectional"))
      (node (ref "J2") (pin "1") (pinfunction "1_1") (pintype "bidirectional"))
      (node (ref "J2") (pin "10") (pinfunction "10_10") (pintype "bidirectional"))
      (node (ref "J2") (pin "13") (pinfunction "13_13") (pintype "bidirectional"))
      (node (ref "J2") (pin "16") (pinfunction "16_16") (pintype "bidirectional"))
      (node (ref "J2") (pin "19") (pinfunction "19_19") (pintype "bidirectional"))
      (node (ref "J2") (pin "22") (pinfunction "22_22") (pintype "bidirectional"))
      (node (ref "J2") (pin "25") (pinfunction "25_25") (pintype "bidirectional"))
      (node (ref "J2") (pin "4") (pinfunction "4_4") (pintype "bidirectional"))
      (node (ref "J2") (pin "7") (pinfunction "7_7") (pintype "bidirectional"))
      (node (ref "J3") (pin "1") (pinfunction "1_1") (pintype "bidirectional"))
      (node (ref "J3") (pin "10") (pinfunction "10_10") (pintype "bidirectional"))
      (node (ref "J3") (pin "13") (pinfunction "13_13") (pintype "bidirectional"))
      (node (ref "J3") (pin "16") (pinfunction "16_16") (pintype "bidirectional"))
      (node (ref "J3") (pin "19") (pinfunction "19_19") (pintype "bidirectional"))
      (node (ref "J3") (pin "22") (pinfunction "22_22") (pintype "bidirectional"))
      (node (ref "J3") (pin "25") (pinfunction "25_25") (pintype "bidirectional"))
      (node (ref "J3") (pin "4") (pinfunction "4_4") (pintype "bidirectional"))
      (node (ref "J3") (pin "7") (pinfunction "7_7") (pintype "bidirectional"))
      (node (ref "J4") (pin "69") (pinfunction "69_69") (pintype "passive"))
      (node (ref "J4") (pin "70") (pinfunction "70_70") (pintype "passive"))
      (node (ref "J4") (pin "71") (pinfunction "71_71") (pintype "passive"))
      (node (ref "J4") (pin "72") (pinfunction "72_72") (pintype "passive"))
      (node (ref "J5") (pin "1") (pinfunction "1_1") (pintype "bidirectional"))
      (node (ref "J5") (pin "10") (pinfunction "10_10") (pintype "bidirectional"))
      (node (ref "J5") (pin "13") (pinfunction "13_13") (pintype "bidirectional"))
      (node (ref "J5") (pin "16") (pinfunction "16_16") (pintype "bidirectional"))
      (node (ref "J5") (pin "19") (pinfunction "19_19") (pintype "bidirectional"))
      (node (ref "J5") (pin "22") (pinfunction "22_22") (pintype "bidirectional"))
      (node (ref "J5") (pin "25") (pinfunction "25_25") (pintype "bidirectional"))
      (node (ref "J5") (pin "4") (pinfunction "4_4") (pintype "bidirectional"))
      (node (ref "J5") (pin "7") (pinfunction "7_7") (pintype "bidirectional"))
      (node (ref "J6") (pin "1") (pinfunction "1_1") (pintype "bidirectional"))
      (node (ref "J6") (pin "10") (pinfunction "10_10") (pintype "bidirectional"))
      (node (ref "J6") (pin "13") (pinfunction "13_13") (pintype "bidirectional"))
      (node (ref "J6") (pin "16") (pinfunction "16_16") (pintype "bidirectional"))
      (node (ref "J6") (pin "19") (pinfunction "19_19") (pintype "bidirectional"))
      (node (ref "J6") (pin "22") (pinfunction "22_22") (pintype "bidirectional"))
      (node (ref "J6") (pin "25") (pinfunction "25_25") (pintype "bidirectional"))
      (node (ref "J6") (pin "4") (pinfunction "4_4") (pintype "bidirectional"))
      (node (ref "J6") (pin "7") (pinfunction "7_7") (pintype "bidirectional"))
      (node (ref "J7") (pin "1") (pinfunction "1_1") (pintype "bidirectional"))
      (node (ref "J7") (pin "10") (pinfunction "10_10") (pintype "bidirectional"))
      (node (ref "J7") (pin "13") (pinfunction "13_13") (pintype "bidirectional"))
      (node (ref "J7") (pin "16") (pinfunction "16_16") (pintype "bidirectional"))
      (node (ref "J7") (pin "19") (pinfunction "19_19") (pintype "bidirectional"))
      (node (ref "J7") (pin "22") (pinfunction "22_22") (pintype "bidirectional"))
      (node (ref "J7") (pin "25") (pinfunction "25_25") (pintype "bidirectional"))
      (node (ref "J7") (pin "4") (pinfunction "4_4") (pintype "bidirectional"))
      (node (ref "J7") (pin "7") (pinfunction "7_7") (pintype "bidirectional"))
      (node (ref "J8") (pin "1") (pinfunction "1_1") (pintype "bidirectional"))
      (node (ref "J8") (pin "10") (pinfunction "10_10") (pintype "bidirectional"))
      (node (ref "J8") (pin "13") (pinfunction "13_13") (pintype "bidirectional"))
      (node (ref "J8") (pin "16") (pinfunction "16_16") (pintype "bidirectional"))
      (node (ref "J8") (pin "19") (pinfunction "19_19") (pintype "bidirectional"))
      (node (ref "J8") (pin "22") (pinfunction "22_22") (pintype "bidirectional"))
      (node (ref "J8") (pin "25") (pinfunction "25_25") (pintype "bidirectional"))
      (node (ref "J8") (pin "4") (pinfunction "4_4") (pintype "bidirectional"))
      (node (ref "J8") (pin "7") (pinfunction "7_7") (pintype "bidirectional"))
      (node (ref "J9") (pin "1") (pinfunction "1_1") (pintype "bidirectional"))
      (node (ref "J9") (pin "10") (pinfunction "10_10") (pintype "bidirectional"))
      (node (ref "J9") (pin "13") (pinfunction "13_13") (pintype "bidirectional"))
      (node (ref "J9") (pin "16") (pinfunction "16_16") (pintype "bidirectional"))
      (node (ref "J9") (pin "19") (pinfunction "19_19") (pintype "bidirectional"))
      (node (ref "J9") (pin "22") (pinfunction "22_22") (pintype "bidirectional"))
      (node (ref "J9") (pin "25") (pinfunction "25_25") (pintype "bidirectional"))
      (node (ref "J9") (pin "4") (pinfunction "4_4") (pintype "bidirectional"))
      (node (ref "J9") (pin "7") (pinfunction "7_7") (pintype "bidirectional"))
      (node (ref "R14") (pin "1") (pinfunction "1_1") (pintype "passive"))
      (node (ref "R19") (pin "1") (pinfunction "1_1") (pintype "passive"))
      (node (ref "R20") (pin "1") (pinfunction "1_1") (pintype "passive"))
      (node (ref "R22") (pin "1") (pinfunction "1_1") (pintype "passive"))
      (node (ref "R28") (pin "1") (pinfunction "1_1") (pintype "passive"))
      (node (ref "R5") (pin "1") (pinfunction "1_1") (pintype "passive"))
      (node (ref "R6") (pin "1") (pinfunction "1_1") (pintype "passive"))
      (node (ref "R8") (pin "1") (pinfunction "1_1") (pintype "passive"))
    )
    (net (code "150") (name "Net-(IC1-A0)") (class "Default")
      (node (ref "IC1") (pin "22") (pinfunction "A0_22") (pintype "input"))
      (node (ref "R8") (pin "2") (pinfunction "2_2") (pintype "passive"))
    )
    (net (code "151") (name "Net-(IC1-A1)") (class "Default")
      (node (ref "IC1") (pin "23") (pinfunction "A1_23") (pintype "input"))
      (node (ref "R6") (pin "2") (pinfunction "2_2") (pintype "passive"))
    )
    (net (code "152") (name "Net-(IC1-A2)") (class "Default")
      (node (ref "IC1") (pin "18") (pinfunction "A2_18") (pintype "input"))
      (node (ref "R5") (pin "2") (pinfunction "2_2") (pintype "passive"))
    )
    (net (code "153") (name "Net-(IC1-SC0)") (class "Default")
      (node (ref "IC1") (pin "2") (pinfunction "SC0_2") (pintype "bidirectional"))
      (node (ref "IC2") (pin "1") (pinfunction "SCL_1") (pintype "input"))
      (node (ref "R1") (pin "1") (pinfunction "1_1") (pintype "passive"))
    )
    (net (code "154") (name "Net-(IC1-SD0)") (class "Default")
      (node (ref "IC1") (pin "1") (pinfunction "SD0_1") (pintype "bidirectional"))
      (node (ref "IC2") (pin "3") (pinfunction "SDA_3") (pintype "bidirectional"))
      (node (ref "R2") (pin "1") (pinfunction "1_1") (pintype "passive"))
    )
    (net (code "155") (name "Net-(IC3-A0)") (class "Default")
      (node (ref "IC3") (pin "22") (pinfunction "A0_22") (pintype "input"))
      (node (ref "R22") (pin "2") (pinfunction "2_2") (pintype "passive"))
    )
    (net (code "156") (name "Net-(IC3-A1)") (class "Default")
      (node (ref "IC3") (pin "23") (pinfunction "A1_23") (pintype "input"))
      (node (ref "R20") (pin "2") (pinfunction "2_2") (pintype "passive"))
    )
    (net (code "157") (name "Net-(IC3-A2)") (class "Default")
      (node (ref "IC3") (pin "18") (pinfunction "A2_18") (pintype "input"))
      (node (ref "R19") (pin "2") (pinfunction "2_2") (pintype "passive"))
    )
    (net (code "158") (name "Net-(IC3-SC0)") (class "Default")
      (node (ref "IC3") (pin "2") (pinfunction "SC0_2") (pintype "bidirectional"))
      (node (ref "IC4") (pin "1") (pinfunction "SCL_1") (pintype "input"))
      (node (ref "R15") (pin "1") (pinfunction "1_1") (pintype "passive"))
    )
    (net (code "159") (name "Net-(IC3-SD0)") (class "Default")
      (node (ref "IC3") (pin "1") (pinfunction "SD0_1") (pintype "bidirectional"))
      (node (ref "IC4") (pin "3") (pinfunction "SDA_3") (pintype "bidirectional"))
      (node (ref "R16") (pin "1") (pinfunction "1_1") (pintype "passive"))
    )
    (net (code "160") (name "Net-(J4A-18)") (class "Default")
      (node (ref "J4") (pin "L18") (pinfunction "18_L18") (pintype "bidirectional"))
      (node (ref "R14") (pin "2") (pinfunction "2_2") (pintype "passive"))
    )
    (net (code "161") (name "Net-(J4B-18)") (class "Default")
      (node (ref "J4") (pin "U18") (pinfunction "18_U18") (pintype "bidirectional"))
      (node (ref "R28") (pin "2") (pinfunction "2_2") (pintype "passive"))
    )
    (net (code "162") (name "P3V3_MP1") (class "Default")
      (node (ref "C1") (pin "2") (pinfunction "2_2") (pintype "passive"))
      (node (ref "C2") (pin "2") (pinfunction "2_2") (pintype "passive"))
      (node (ref "C3") (pin "2") (pinfunction "2_2") (pintype "passive"))
      (node (ref "C4") (pin "2") (pinfunction "2_2") (pintype "passive"))
      (node (ref "C5") (pin "2") (pinfunction "2_2") (pintype "passive"))
      (node (ref "C6") (pin "1") (pinfunction "1_1") (pintype "passive"))
      (node (ref "IC1") (pin "21") (pinfunction "VCC_21") (pintype "power_in"))
      (node (ref "IC1") (pin "24") (pinfunction "~{RESET}_24") (pintype "input"))
      (node (ref "IC2") (pin "4") (pinfunction "VCC_4") (pintype "power_in"))
      (node (ref "J1") (pin "30") (pinfunction "30_30") (pintype "bidirectional"))
      (node (ref "J2") (pin "30") (pinfunction "30_30") (pintype "bidirectional"))
      (node (ref "J3") (pin "30") (pinfunction "30_30") (pintype "bidirectional"))
      (node (ref "J4") (pin "L52") (pinfunction "52_L52") (pintype "bidirectional"))
      (node (ref "J5") (pin "30") (pinfunction "30_30") (pintype "bidirectional"))
      (node (ref "R1") (pin "2") (pinfunction "2_2") (pintype "passive"))
      (node (ref "R10") (pin "2") (pinfunction "2_2") (pintype "passive"))
      (node (ref "R11") (pin "2") (pinfunction "2_2") (pintype "passive"))
      (node (ref "R12") (pin "2") (pinfunction "2_2") (pintype "passive"))
      (node (ref "R13") (pin "2") (pinfunction "2_2") (pintype "passive"))
      (node (ref "R2") (pin "2") (pinfunction "2_2") (pintype "passive"))
      (node (ref "R3") (pin "2") (pinfunction "2_2") (pintype "passive"))
      (node (ref "R4") (pin "2") (pinfunction "2_2") (pintype "passive"))
      (node (ref "R7") (pin "2") (pinfunction "2_2") (pintype "passive"))
      (node (ref "R9") (pin "2") (pinfunction "2_2") (pintype "passive"))
    )
    (net (code "163") (name "P3V3_MP2") (class "Default")
      (node (ref "C10") (pin "2") (pinfunction "2_2") (pintype "passive"))
      (node (ref "C11") (pin "2") (pinfunction "2_2") (pintype "passive"))
      (node (ref "C12") (pin "1") (pinfunction "1_1") (pintype "passive"))
      (node (ref "C7") (pin "2") (pinfunction "2_2") (pintype "passive"))
      (node (ref "C8") (pin "2") (pinfunction "2_2") (pintype "passive"))
      (node (ref "C9") (pin "2") (pinfunction "2_2") (pintype "passive"))
      (node (ref "IC3") (pin "21") (pinfunction "VCC_21") (pintype "power_in"))
      (node (ref "IC3") (pin "24") (pinfunction "~{RESET}_24") (pintype "input"))
      (node (ref "IC4") (pin "4") (pinfunction "VCC_4") (pintype "power_in"))
      (node (ref "J4") (pin "U52") (pinfunction "52_U52") (pintype "bidirectional"))
      (node (ref "J6") (pin "30") (pinfunction "30_30") (pintype "bidirectional"))
      (node (ref "J7") (pin "30") (pinfunction "30_30") (pintype "bidirectional"))
      (node (ref "J8") (pin "30") (pinfunction "30_30") (pintype "bidirectional"))
      (node (ref "J9") (pin "30") (pinfunction "30_30") (pintype "bidirectional"))
      (node (ref "R15") (pin "2") (pinfunction "2_2") (pintype "passive"))
      (node (ref "R16") (pin "2") (pinfunction "2_2") (pintype "passive"))
      (node (ref "R17") (pin "2") (pinfunction "2_2") (pintype "passive"))
      (node (ref "R18") (pin "2") (pinfunction "2_2") (pintype "passive"))
      (node (ref "R21") (pin "2") (pinfunction "2_2") (pintype "passive"))
      (node (ref "R23") (pin "2") (pinfunction "2_2") (pintype "passive"))
      (node (ref "R24") (pin "2") (pinfunction "2_2") (pintype "passive"))
      (node (ref "R25") (pin "2") (pinfunction "2_2") (pintype "passive"))
      (node (ref "R26") (pin "2") (pinfunction "2_2") (pintype "passive"))
      (node (ref "R27") (pin "2") (pinfunction "2_2") (pintype "passive"))
    )
    (net (code "164") (name "P5V0") (class "Default")
      (node (ref "J10") (pin "a32") (pinfunction "a32_a32") (pintype "bidirectional"))
      (node (ref "J10") (pin "b32") (pinfunction "b32_b32") (pintype "bidirectional"))
      (node (ref "J10") (pin "c32") (pinfunction "c32_c32") (pintype "bidirectional"))
    )
    (net (code "165") (name "P12V0") (class "Default")
      (node (ref "C13") (pin "1") (pinfunction "1_1") (pintype "passive"))
      (node (ref "J1") (pin "28") (pinfunction "28_28") (pintype "bidirectional"))
      (node (ref "J1") (pin "29") (pinfunction "29_29") (pintype "bidirectional"))
      (node (ref "J10") (pin "b31") (pinfunction "b31_b31") (pintype "bidirectional"))
      (node (ref "J10") (pin "c31") (pinfunction "c31_c31") (pintype "bidirectional"))
      (node (ref "J11") (pin "1") (pinfunction "1_1") (pintype "bidirectional"))
      (node (ref "J2") (pin "28") (pinfunction "28_28") (pintype "bidirectional"))
      (node (ref "J2") (pin "29") (pinfunction "29_29") (pintype "bidirectional"))
      (node (ref "J3") (pin "28") (pinfunction "28_28") (pintype "bidirectional"))
      (node (ref "J3") (pin "29") (pinfunction "29_29") (pintype "bidirectional"))
      (node (ref "J5") (pin "28") (pinfunction "28_28") (pintype "bidirectional"))
      (node (ref "J5") (pin "29") (pinfunction "29_29") (pintype "bidirectional"))
      (node (ref "J6") (pin "28") (pinfunction "28_28") (pintype "bidirectional"))
      (node (ref "J6") (pin "29") (pinfunction "29_29") (pintype "bidirectional"))
      (node (ref "J7") (pin "28") (pinfunction "28_28") (pintype "bidirectional"))
      (node (ref "J7") (pin "29") (pinfunction "29_29") (pintype "bidirectional"))
      (node (ref "J8") (pin "28") (pinfunction "28_28") (pintype "bidirectional"))
      (node (ref "J8") (pin "29") (pinfunction "29_29") (pintype "bidirectional"))
      (node (ref "J9") (pin "28") (pinfunction "28_28") (pintype "bidirectional"))
      (node (ref "J9") (pin "29") (pinfunction "29_29") (pintype "bidirectional"))
    )
    (net (code "166") (name "unconnected-(IC1-SC5-Pad13)") (class "Default")
      (node (ref "IC1") (pin "13") (pinfunction "SC5_13") (pintype "bidirectional"))
    )
    (net (code "167") (name "unconnected-(IC1-SC6-Pad15)") (class "Default")
      (node (ref "IC1") (pin "15") (pinfunction "SC6_15") (pintype "bidirectional"))
    )
    (net (code "168") (name "unconnected-(IC1-SC7-Pad17)") (class "Default")
      (node (ref "IC1") (pin "17") (pinfunction "SC7_17") (pintype "bidirectional"))
    )
    (net (code "169") (name "unconnected-(IC1-SD5-Pad12)") (class "Default")
      (node (ref "IC1") (pin "12") (pinfunction "SD5_12") (pintype "bidirectional"))
    )
    (net (code "170") (name "unconnected-(IC1-SD6-Pad14)") (class "Default")
      (node (ref "IC1") (pin "14") (pinfunction "SD6_14") (pintype "bidirectional"))
    )
    (net (code "171") (name "unconnected-(IC1-SD7-Pad16)") (class "Default")
      (node (ref "IC1") (pin "16") (pinfunction "SD7_16") (pintype "bidirectional"))
    )
    (net (code "172") (name "unconnected-(IC2-NC-Pad5)") (class "Default")
      (node (ref "IC2") (pin "5") (pinfunction "NC_5") (pintype "passive"))
    )
    (net (code "173") (name "unconnected-(IC3-SC5-Pad13)") (class "Default")
      (node (ref "IC3") (pin "13") (pinfunction "SC5_13") (pintype "bidirectional"))
    )
    (net (code "174") (name "unconnected-(IC3-SC6-Pad15)") (class "Default")
      (node (ref "IC3") (pin "15") (pinfunction "SC6_15") (pintype "bidirectional"))
    )
    (net (code "175") (name "unconnected-(IC3-SC7-Pad17)") (class "Default")
      (node (ref "IC3") (pin "17") (pinfunction "SC7_17") (pintype "bidirectional"))
    )
    (net (code "176") (name "unconnected-(IC3-SD5-Pad12)") (class "Default")
      (node (ref "IC3") (pin "12") (pinfunction "SD5_12") (pintype "bidirectional"))
    )
    (net (code "177") (name "unconnected-(IC3-SD6-Pad14)") (class "Default")
      (node (ref "IC3") (pin "14") (pinfunction "SD6_14") (pintype "bidirectional"))
    )
    (net (code "178") (name "unconnected-(IC3-SD7-Pad16)") (class "Default")
      (node (ref "IC3") (pin "16") (pinfunction "SD7_16") (pintype "bidirectional"))
    )
    (net (code "179") (name "unconnected-(IC4-NC-Pad5)") (class "Default")
      (node (ref "IC4") (pin "5") (pinfunction "NC_5") (pintype "passive"))
    )
    (net (code "180") (name "unconnected-(J10-Pada1)") (class "Default")
      (node (ref "J10") (pin "a1") (pinfunction "a1_a1") (pintype "bidirectional"))
    )
    (net (code "181") (name "unconnected-(J10-Pada2)") (class "Default")
      (node (ref "J10") (pin "a2") (pinfunction "a2_a2") (pintype "bidirectional"))
    )
    (net (code "182") (name "unconnected-(J10-Pada3)") (class "Default")
      (node (ref "J10") (pin "a3") (pinfunction "a3_a3") (pintype "bidirectional"))
    )
    (net (code "183") (name "unconnected-(J10-Pada4)") (class "Default")
      (node (ref "J10") (pin "a4") (pinfunction "a4_a4") (pintype "bidirectional"))
    )
    (net (code "184") (name "unconnected-(J10-Pada5)") (class "Default")
      (node (ref "J10") (pin "a5") (pinfunction "a5_a5") (pintype "bidirectional"))
    )
    (net (code "185") (name "unconnected-(J10-Pada6)") (class "Default")
      (node (ref "J10") (pin "a6") (pinfunction "a6_a6") (pintype "bidirectional"))
    )
    (net (code "186") (name "unconnected-(J10-Pada7)") (class "Default")
      (node (ref "J10") (pin "a7") (pinfunction "a7_a7") (pintype "bidirectional"))
    )
    (net (code "187") (name "unconnected-(J10-Pada8)") (class "Default")
      (node (ref "J10") (pin "a8") (pinfunction "a8_a8") (pintype "bidirectional"))
    )
    (net (code "188") (name "unconnected-(J10-Pada10)") (class "Default")
      (node (ref "J10") (pin "a10") (pinfunction "a10_a10") (pintype "bidirectional"))
    )
    (net (code "189") (name "unconnected-(J10-Pada12)") (class "Default")
      (node (ref "J10") (pin "a12") (pinfunction "a12_a12") (pintype "bidirectional"))
    )
    (net (code "190") (name "unconnected-(J10-Pada13)") (class "Default")
      (node (ref "J10") (pin "a13") (pinfunction "a13_a13") (pintype "bidirectional"))
    )
    (net (code "191") (name "unconnected-(J10-Pada14)") (class "Default")
      (node (ref "J10") (pin "a14") (pinfunction "a14_a14") (pintype "bidirectional"))
    )
    (net (code "192") (name "unconnected-(J10-Pada15)") (class "Default")
      (node (ref "J10") (pin "a15") (pinfunction "a15_a15") (pintype "bidirectional"))
    )
    (net (code "193") (name "unconnected-(J10-Pada16)") (class "Default")
      (node (ref "J10") (pin "a16") (pinfunction "a16_a16") (pintype "bidirectional"))
    )
    (net (code "194") (name "unconnected-(J10-Pada18)") (class "Default")
      (node (ref "J10") (pin "a18") (pinfunction "a18_a18") (pintype "bidirectional"))
    )
    (net (code "195") (name "unconnected-(J10-Pada20)") (class "Default")
      (node (ref "J10") (pin "a20") (pinfunction "a20_a20") (pintype "bidirectional"))
    )
    (net (code "196") (name "unconnected-(J10-Pada21)") (class "Default")
      (node (ref "J10") (pin "a21") (pinfunction "a21_a21") (pintype "bidirectional"))
    )
    (net (code "197") (name "unconnected-(J10-Pada22)") (class "Default")
      (node (ref "J10") (pin "a22") (pinfunction "a22_a22") (pintype "bidirectional"))
    )
    (net (code "198") (name "unconnected-(J10-Pada23)") (class "Default")
      (node (ref "J10") (pin "a23") (pinfunction "a23_a23") (pintype "bidirectional"))
    )
    (net (code "199") (name "unconnected-(J10-Pada24)") (class "Default")
      (node (ref "J10") (pin "a24") (pinfunction "a24_a24") (pintype "bidirectional"))
    )
    (net (code "200") (name "unconnected-(J10-Pada25)") (class "Default")
      (node (ref "J10") (pin "a25") (pinfunction "a25_a25") (pintype "bidirectional"))
    )
    (net (code "201") (name "unconnected-(J10-Pada26)") (class "Default")
      (node (ref "J10") (pin "a26") (pinfunction "a26_a26") (pintype "bidirectional"))
    )
    (net (code "202") (name "unconnected-(J10-Pada27)") (class "Default")
      (node (ref "J10") (pin "a27") (pinfunction "a27_a27") (pintype "bidirectional"))
    )
    (net (code "203") (name "unconnected-(J10-Pada28)") (class "Default")
      (node (ref "J10") (pin "a28") (pinfunction "a28_a28") (pintype "bidirectional"))
    )
    (net (code "204") (name "unconnected-(J10-Pada29)") (class "Default")
      (node (ref "J10") (pin "a29") (pinfunction "a29_a29") (pintype "bidirectional"))
    )
    (net (code "205") (name "unconnected-(J10-Pada30)") (class "Default")
      (node (ref "J10") (pin "a30") (pinfunction "a30_a30") (pintype "bidirectional"))
    )
    (net (code "206") (name "unconnected-(J10-Pada31)") (class "Default")
      (node (ref "J10") (pin "a31") (pinfunction "a31_a31") (pintype "bidirectional"))
    )
    (net (code "207") (name "unconnected-(J10-Padb1)") (class "Default")
      (node (ref "J10") (pin "b1") (pinfunction "b1_b1") (pintype "bidirectional"))
    )
    (net (code "208") (name "unconnected-(J10-Padb3)") (class "Default")
      (node (ref "J10") (pin "b3") (pinfunction "b3_b3") (pintype "bidirectional"))
    )
    (net (code "209") (name "unconnected-(J10-Padb4)") (class "Default")
      (node (ref "J10") (pin "b4") (pinfunction "b4_b4") (pintype "bidirectional"))
    )
    (net (code "210") (name "unconnected-(J10-Padb5)") (class "Default")
      (node (ref "J10") (pin "b5") (pinfunction "b5_b5") (pintype "bidirectional"))
    )
    (net (code "211") (name "unconnected-(J10-Padb6)") (class "Default")
      (node (ref "J10") (pin "b6") (pinfunction "b6_b6") (pintype "bidirectional"))
    )
    (net (code "212") (name "unconnected-(J10-Padb7)") (class "Default")
      (node (ref "J10") (pin "b7") (pinfunction "b7_b7") (pintype "bidirectional"))
    )
    (net (code "213") (name "unconnected-(J10-Padb8)") (class "Default")
      (node (ref "J10") (pin "b8") (pinfunction "b8_b8") (pintype "bidirectional"))
    )
    (net (code "214") (name "unconnected-(J10-Padb9)") (class "Default")
      (node (ref "J10") (pin "b9") (pinfunction "b9_b9") (pintype "bidirectional"))
    )
    (net (code "215") (name "unconnected-(J10-Padb10)") (class "Default")
      (node (ref "J10") (pin "b10") (pinfunction "b10_b10") (pintype "bidirectional"))
    )
    (net (code "216") (name "unconnected-(J10-Padb11)") (class "Default")
      (node (ref "J10") (pin "b11") (pinfunction "b11_b11") (pintype "bidirectional"))
    )
    (net (code "217") (name "unconnected-(J10-Padb13)") (class "Default")
      (node (ref "J10") (pin "b13") (pinfunction "b13_b13") (pintype "bidirectional"))
    )
    (net (code "218") (name "unconnected-(J10-Padb14)") (class "Default")
      (node (ref "J10") (pin "b14") (pinfunction "b14_b14") (pintype "bidirectional"))
    )
    (net (code "219") (name "unconnected-(J10-Padb15)") (class "Default")
      (node (ref "J10") (pin "b15") (pinfunction "b15_b15") (pintype "bidirectional"))
    )
    (net (code "220") (name "unconnected-(J10-Padb16)") (class "Default")
      (node (ref "J10") (pin "b16") (pinfunction "b16_b16") (pintype "bidirectional"))
    )
    (net (code "221") (name "unconnected-(J10-Padb17)") (class "Default")
      (node (ref "J10") (pin "b17") (pinfunction "b17_b17") (pintype "bidirectional"))
    )
    (net (code "222") (name "unconnected-(J10-Padb18)") (class "Default")
      (node (ref "J10") (pin "b18") (pinfunction "b18_b18") (pintype "bidirectional"))
    )
    (net (code "223") (name "unconnected-(J10-Padb19)") (class "Default")
      (node (ref "J10") (pin "b19") (pinfunction "b19_b19") (pintype "bidirectional"))
    )
    (net (code "224") (name "unconnected-(J10-Padb21)") (class "Default")
      (node (ref "J10") (pin "b21") (pinfunction "b21_b21") (pintype "bidirectional"))
    )
    (net (code "225") (name "unconnected-(J10-Padb24)") (class "Default")
      (node (ref "J10") (pin "b24") (pinfunction "b24_b24") (pintype "bidirectional"))
    )
    (net (code "226") (name "unconnected-(J10-Padb25)") (class "Default")
      (node (ref "J10") (pin "b25") (pinfunction "b25_b25") (pintype "bidirectional"))
    )
    (net (code "227") (name "unconnected-(J10-Padb26)") (class "Default")
      (node (ref "J10") (pin "b26") (pinfunction "b26_b26") (pintype "bidirectional"))
    )
    (net (code "228") (name "unconnected-(J10-Padb27)") (class "Default")
      (node (ref "J10") (pin "b27") (pinfunction "b27_b27") (pintype "bidirectional"))
    )
    (net (code "229") (name "unconnected-(J10-Padb28)") (class "Default")
      (node (ref "J10") (pin "b28") (pinfunction "b28_b28") (pintype "bidirectional"))
    )
    (net (code "230") (name "unconnected-(J10-Padb29)") (class "Default")
      (node (ref "J10") (pin "b29") (pinfunction "b29_b29") (pintype "bidirectional"))
    )
    (net (code "231") (name "unconnected-(J10-Padb30)") (class "Default")
      (node (ref "J10") (pin "b30") (pinfunction "b30_b30") (pintype "bidirectional"))
    )
    (net (code "232") (name "unconnected-(J10-Padc1)") (class "Default")
      (node (ref "J10") (pin "c1") (pinfunction "c1_c1") (pintype "bidirectional"))
    )
    (net (code "233") (name "unconnected-(J10-Padc2)") (class "Default")
      (node (ref "J10") (pin "c2") (pinfunction "c2_c2") (pintype "bidirectional"))
    )
    (net (code "234") (name "unconnected-(J10-Padc3)") (class "Default")
      (node (ref "J10") (pin "c3") (pinfunction "c3_c3") (pintype "bidirectional"))
    )
    (net (code "235") (name "unconnected-(J10-Padc4)") (class "Default")
      (node (ref "J10") (pin "c4") (pinfunction "c4_c4") (pintype "bidirectional"))
    )
    (net (code "236") (name "unconnected-(J10-Padc5)") (class "Default")
      (node (ref "J10") (pin "c5") (pinfunction "c5_c5") (pintype "bidirectional"))
    )
    (net (code "237") (name "unconnected-(J10-Padc6)") (class "Default")
      (node (ref "J10") (pin "c6") (pinfunction "c6_c6") (pintype "bidirectional"))
    )
    (net (code "238") (name "unconnected-(J10-Padc7)") (class "Default")
      (node (ref "J10") (pin "c7") (pinfunction "c7_c7") (pintype "bidirectional"))
    )
    (net (code "239") (name "unconnected-(J10-Padc8)") (class "Default")
      (node (ref "J10") (pin "c8") (pinfunction "c8_c8") (pintype "bidirectional"))
    )
    (net (code "240") (name "unconnected-(J10-Padc10)") (class "Default")
      (node (ref "J10") (pin "c10") (pinfunction "c10_c10") (pintype "bidirectional"))
    )
    (net (code "241") (name "unconnected-(J10-Padc11)") (class "Default")
      (node (ref "J10") (pin "c11") (pinfunction "c11_c11") (pintype "bidirectional"))
    )
    (net (code "242") (name "unconnected-(J10-Padc12)") (class "Default")
      (node (ref "J10") (pin "c12") (pinfunction "c12_c12") (pintype "bidirectional"))
    )
    (net (code "243") (name "unconnected-(J10-Padc13)") (class "Default")
      (node (ref "J10") (pin "c13") (pinfunction "c13_c13") (pintype "bidirectional"))
    )
    (net (code "244") (name "unconnected-(J10-Padc14)") (class "Default")
      (node (ref "J10") (pin "c14") (pinfunction "c14_c14") (pintype "bidirectional"))
    )
    (net (code "245") (name "unconnected-(J10-Padc15)") (class "Default")
      (node (ref "J10") (pin "c15") (pinfunction "c15_c15") (pintype "bidirectional"))
    )
    (net (code "246") (name "unconnected-(J10-Padc16)") (class "Default")
      (node (ref "J10") (pin "c16") (pinfunction "c16_c16") (pintype "bidirectional"))
    )
    (net (code "247") (name "unconnected-(J10-Padc17)") (class "Default")
      (node (ref "J10") (pin "c17") (pinfunction "c17_c17") (pintype "bidirectional"))
    )
    (net (code "248") (name "unconnected-(J10-Padc18)") (class "Default")
      (node (ref "J10") (pin "c18") (pinfunction "c18_c18") (pintype "bidirectional"))
    )
    (net (code "249") (name "unconnected-(J10-Padc19)") (class "Default")
      (node (ref "J10") (pin "c19") (pinfunction "c19_c19") (pintype "bidirectional"))
    )
    (net (code "250") (name "unconnected-(J10-Padc20)") (class "Default")
      (node (ref "J10") (pin "c20") (pinfunction "c20_c20") (pintype "bidirectional"))
    )
    (net (code "251") (name "unconnected-(J10-Padc21)") (class "Default")
      (node (ref "J10") (pin "c21") (pinfunction "c21_c21") (pintype "bidirectional"))
    )
    (net (code "252") (name "unconnected-(J10-Padc22)") (class "Default")
      (node (ref "J10") (pin "c22") (pinfunction "c22_c22") (pintype "bidirectional"))
    )
    (net (code "253") (name "unconnected-(J10-Padc23)") (class "Default")
      (node (ref "J10") (pin "c23") (pinfunction "c23_c23") (pintype "bidirectional"))
    )
    (net (code "254") (name "unconnected-(J10-Padc24)") (class "Default")
      (node (ref "J10") (pin "c24") (pinfunction "c24_c24") (pintype "bidirectional"))
    )
    (net (code "255") (name "unconnected-(J10-Padc25)") (class "Default")
      (node (ref "J10") (pin "c25") (pinfunction "c25_c25") (pintype "bidirectional"))
    )
    (net (code "256") (name "unconnected-(J10-Padc26)") (class "Default")
      (node (ref "J10") (pin "c26") (pinfunction "c26_c26") (pintype "bidirectional"))
    )
    (net (code "257") (name "unconnected-(J10-Padc27)") (class "Default")
      (node (ref "J10") (pin "c27") (pinfunction "c27_c27") (pintype "bidirectional"))
    )
    (net (code "258") (name "unconnected-(J10-Padc28)") (class "Default")
      (node (ref "J10") (pin "c28") (pinfunction "c28_c28") (pintype "bidirectional"))
    )
    (net (code "259") (name "unconnected-(J10-Padc29)") (class "Default")
      (node (ref "J10") (pin "c29") (pinfunction "c29_c29") (pintype "bidirectional"))
    )
    (net (code "260") (name "unconnected-(J10-Padc30)") (class "Default")
      (node (ref "J10") (pin "c30") (pinfunction "c30_c30") (pintype "bidirectional"))
    )
    (net (code "261") (name "unconnected-(J11-Pad3)") (class "Default")
      (node (ref "J11") (pin "3") (pinfunction "3_3") (pintype "bidirectional"))
    )
  )
)
